# Main.net
KiCad netlist of a schematic drawn in EAGLE
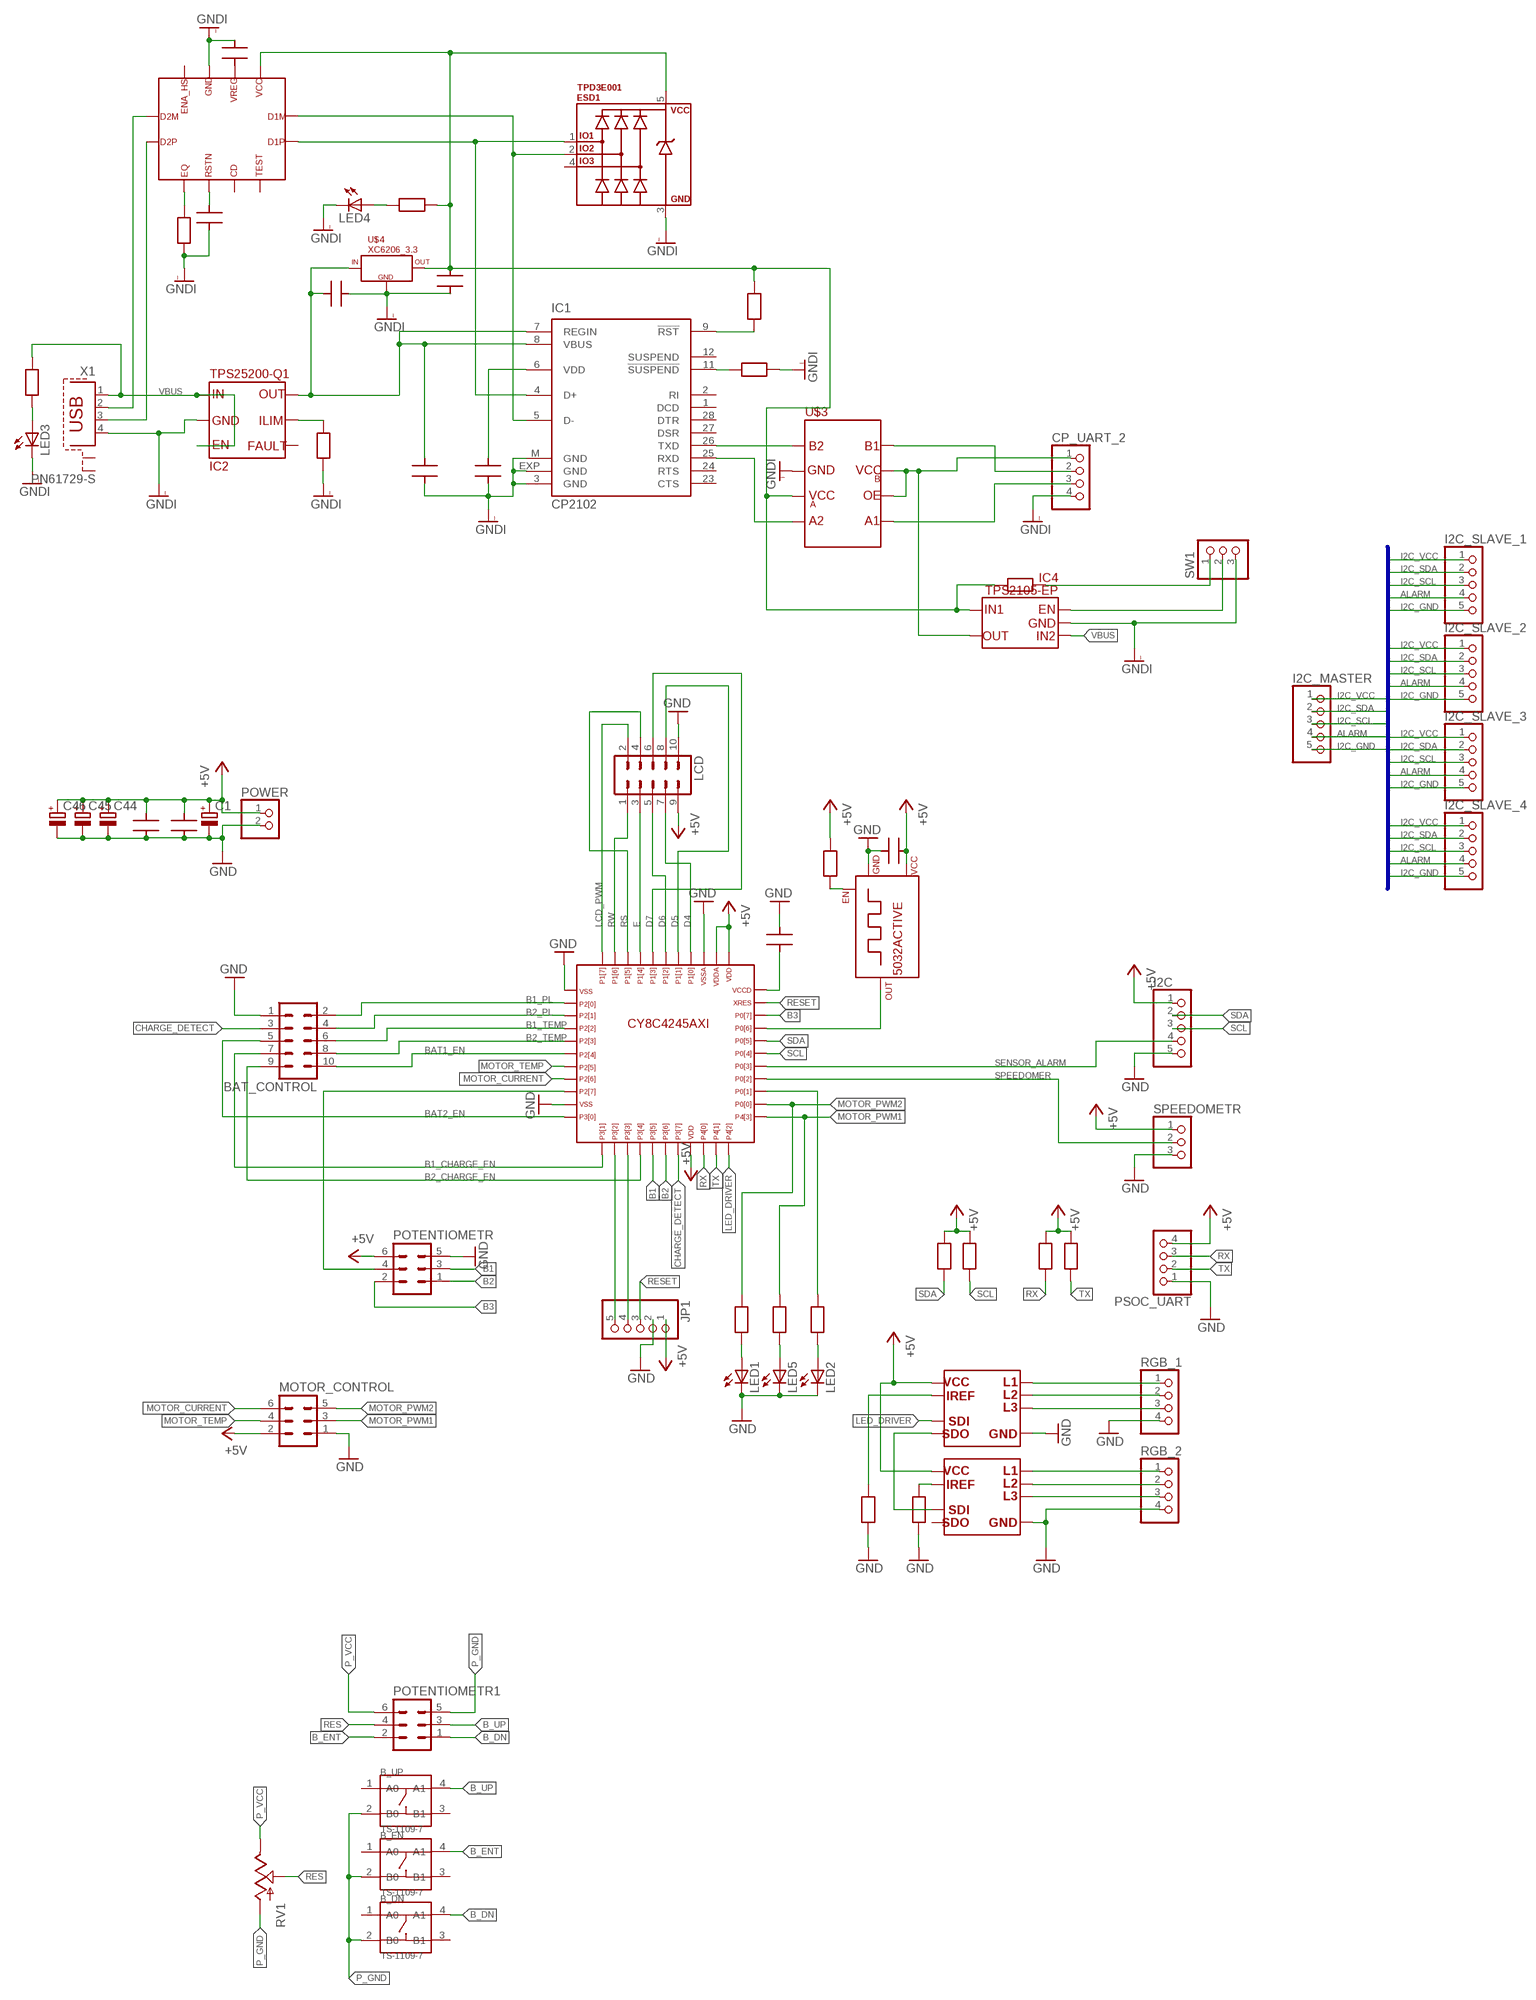
[diagram p0: schematic, sheet 1]
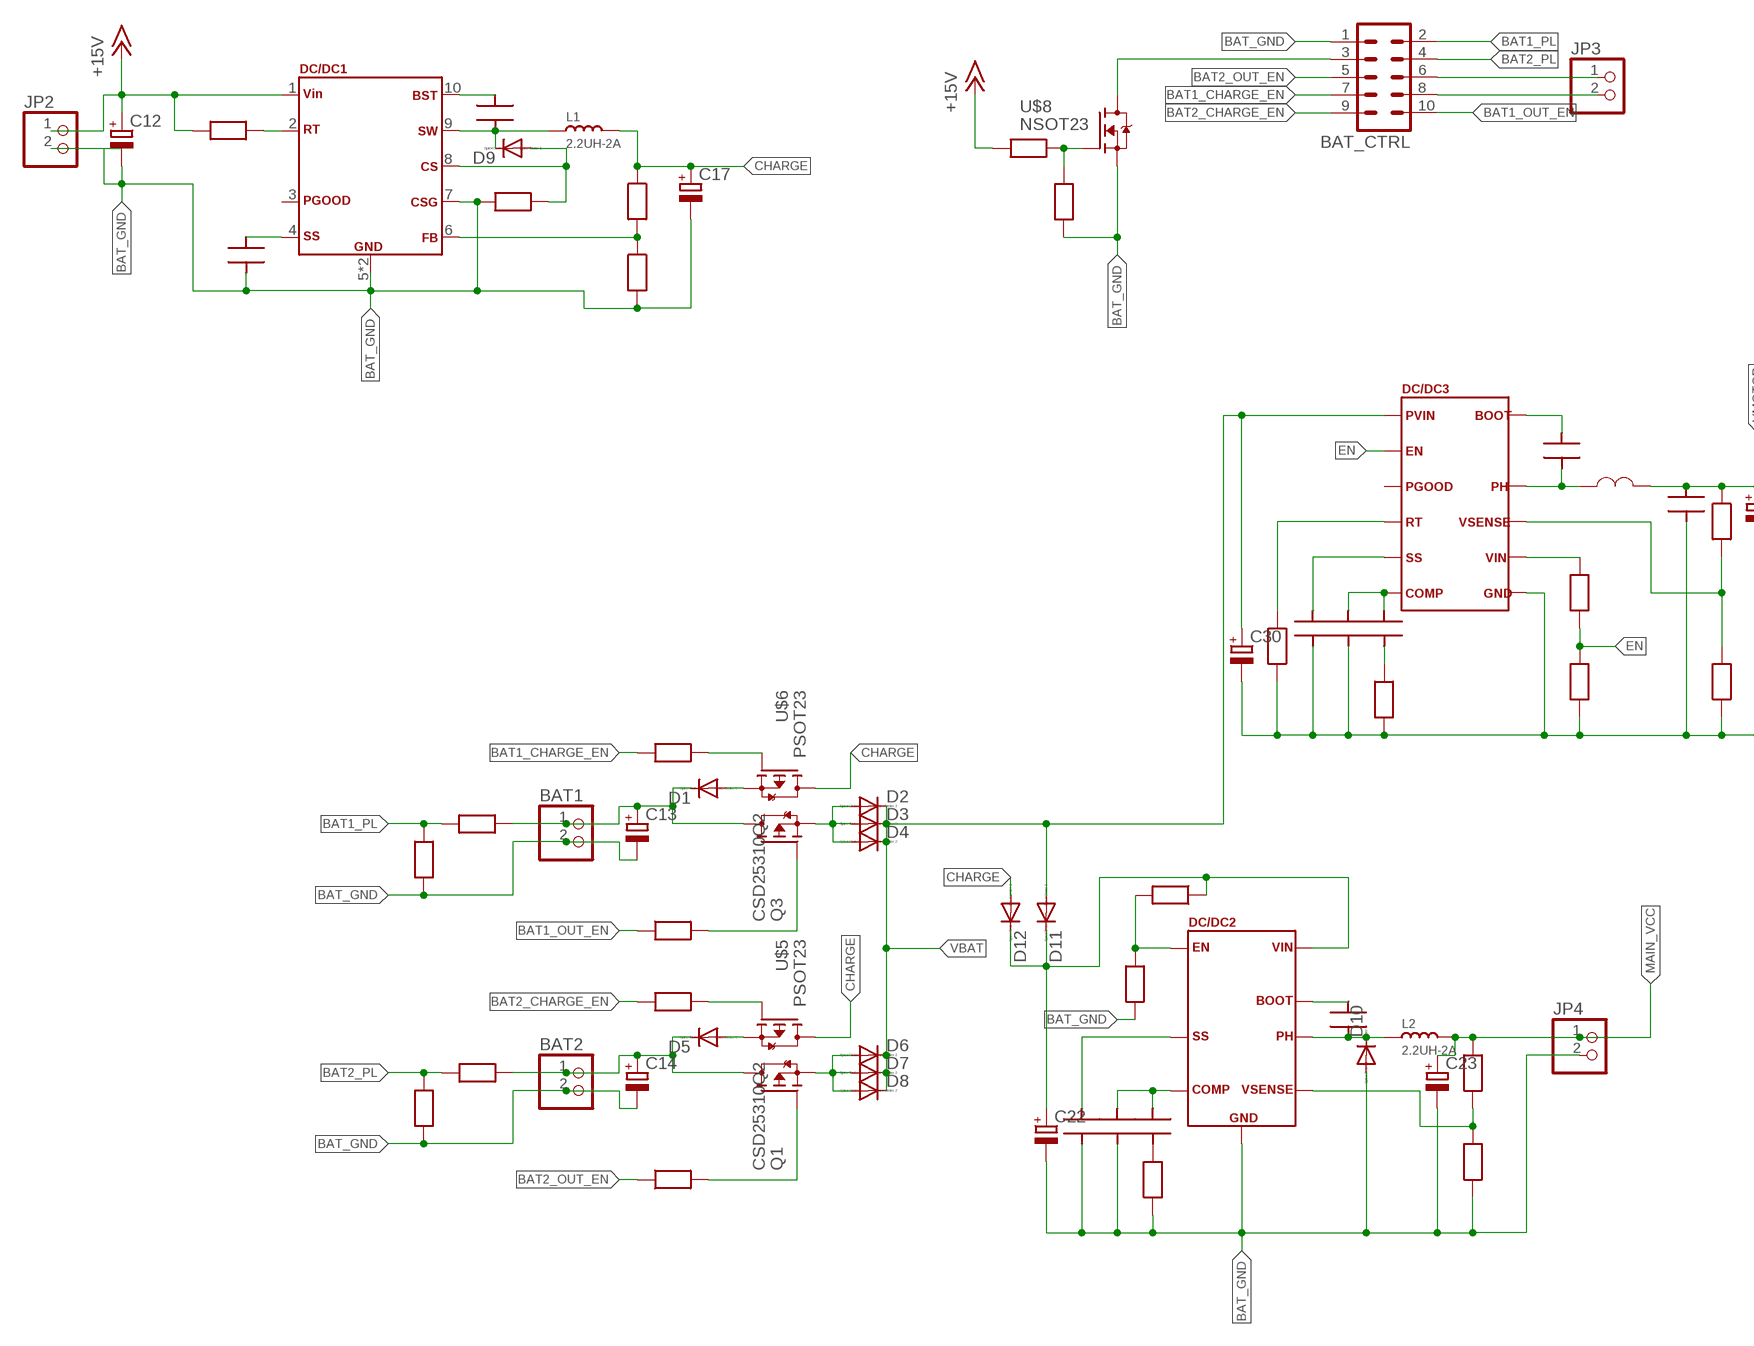
[diagram p1: schematic, sheet 2, part 1 of 2]
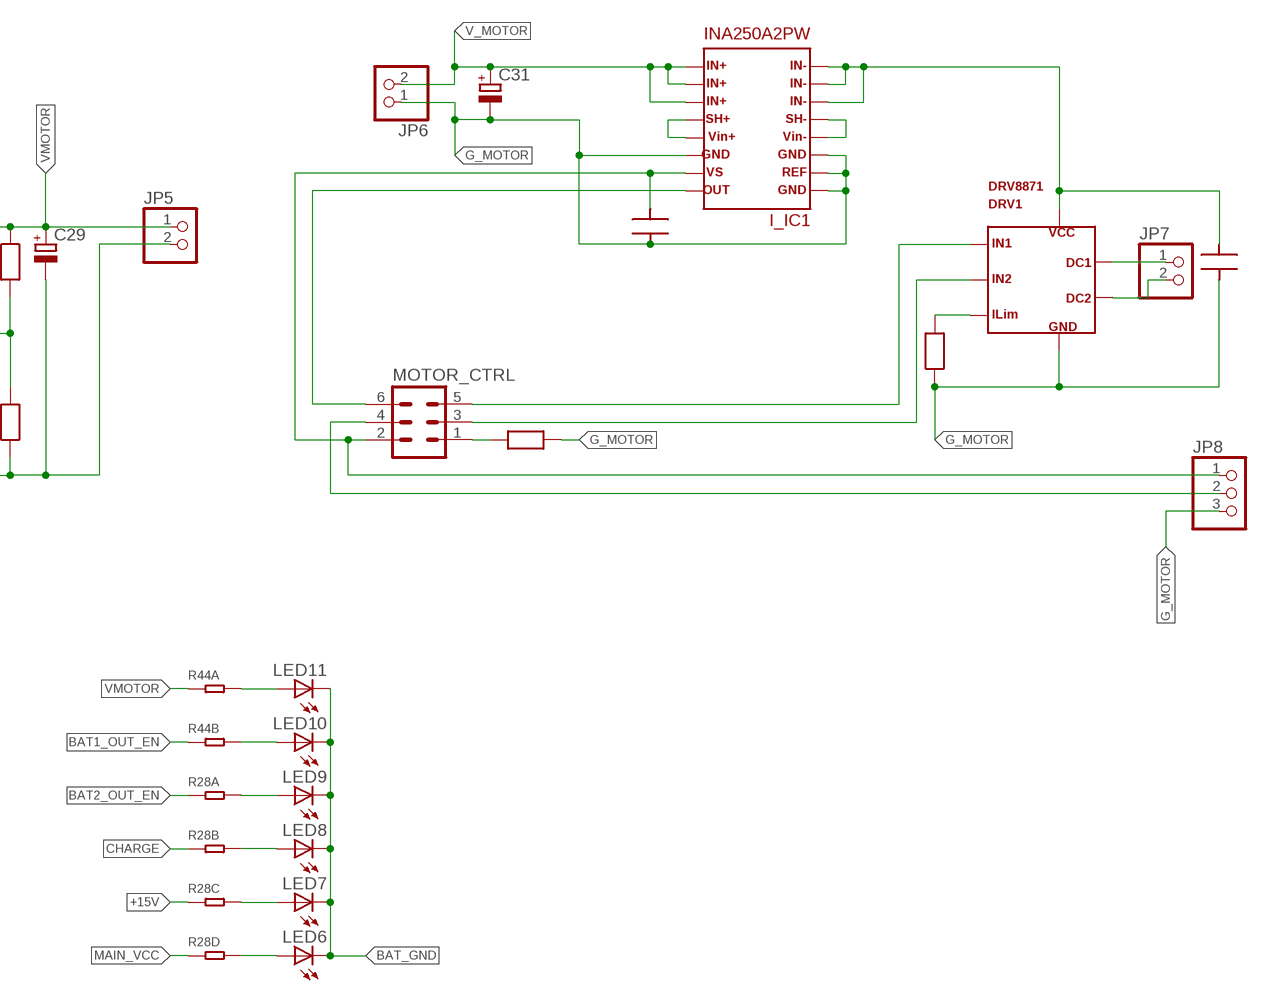
[diagram p2: schematic, sheet 2, part 2 of 2]
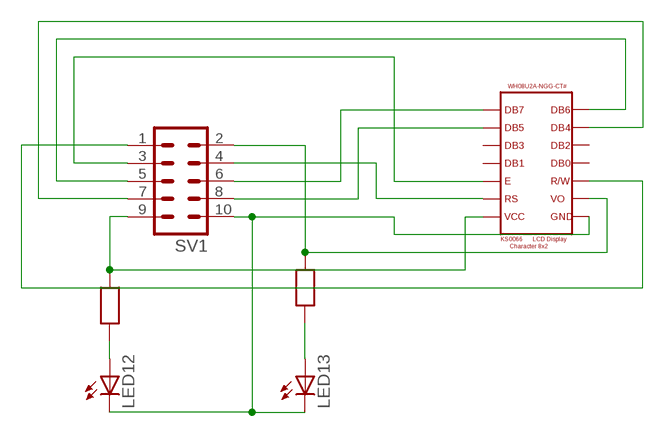
[diagram p3: schematic, sheet 3]
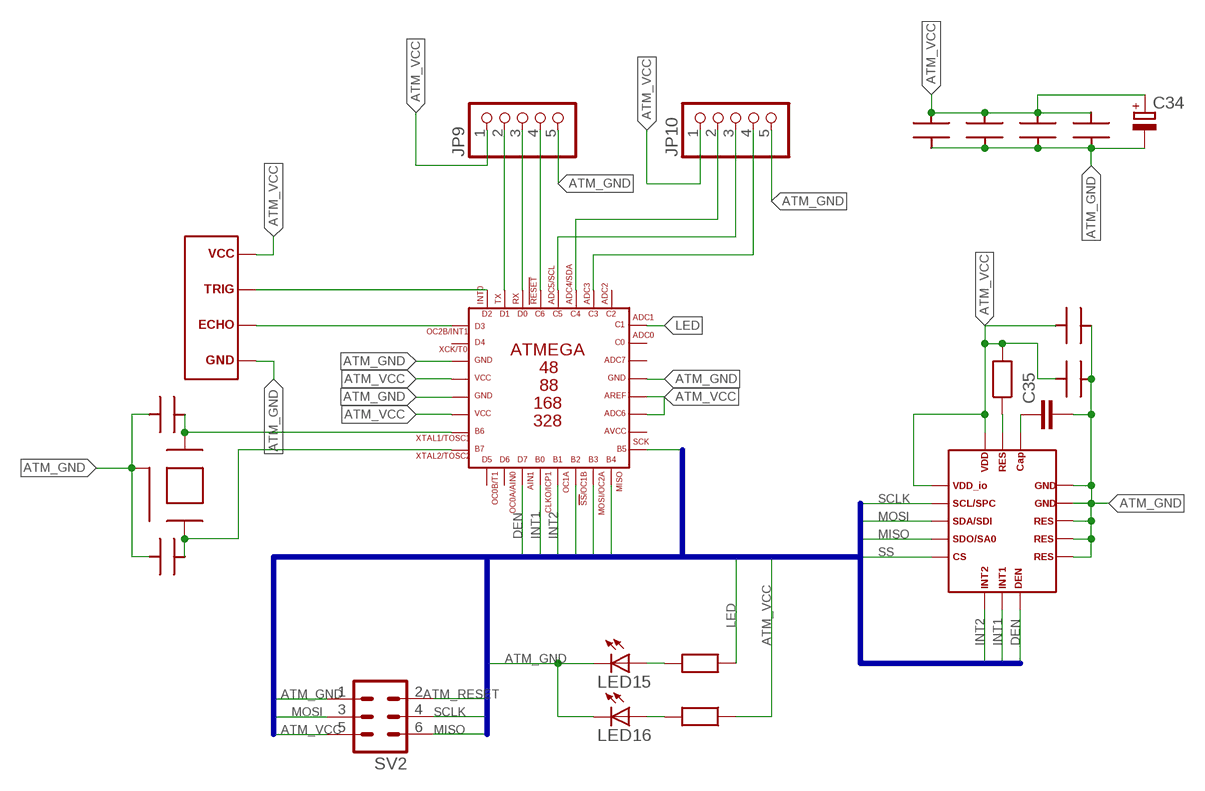
[diagram p4: schematic, sheet 4]

(export (version "E")
  (design (tool "Eeschema 10.0.6"))
  (components
    (comp (ref "LED12")
      (value "LEDCHIPLED_1206")
      (footprint "eagle-import:CHIPLED_1206")
      (libsource (lib "eagle-import") (part "LEDCHIPLED_1206"))
    )
    (comp (ref "LED13")
      (value "LEDCHIPLED_1206")
      (footprint "eagle-import:CHIPLED_1206")
      (libsource (lib "eagle-import") (part "LEDCHIPLED_1206"))
    )
    (comp (ref "R47")
      (value "RES0603")
      (footprint "eagle-import:R0603")
      (libsource (lib "eagle-import") (part "RES0603"))
    )
    (comp (ref "R48")
      (value "RES0603")
      (footprint "eagle-import:R0603")
      (libsource (lib "eagle-import") (part "RES0603"))
    )
    (comp (ref "SV1")
      (value "ML10")
      (footprint "eagle-import:ML10")
      (libsource (lib "eagle-import") (part "ML10"))
    )
    (comp (ref "U$7")
      (value "8X2_KS066")
      (footprint "eagle-import:7X2")
      (libsource (lib "eagle-import") (part "8X2_KS066"))
    )
    (comp (ref "C34")
      (value "CPOL-EU153CLV-0505")
      (footprint "eagle-import:153CLV-0505")
      (libsource (lib "eagle-import") (part "CPOL-EU153CLV-0505"))
    )
    (comp (ref "C35")
      (value "C-EUC1206")
      (footprint "eagle-import:C1206")
      (libsource (lib "eagle-import") (part "C-EUC1206"))
    )
    (comp (ref "C36")
      (value "CAP0603")
      (footprint "eagle-import:C0603")
      (libsource (lib "eagle-import") (part "CAP0603"))
    )
    (comp (ref "C37")
      (value "CAP0603")
      (footprint "eagle-import:C0603")
      (libsource (lib "eagle-import") (part "CAP0603"))
    )
    (comp (ref "C38")
      (value "CAP0603")
      (footprint "eagle-import:C0603")
      (libsource (lib "eagle-import") (part "CAP0603"))
    )
    (comp (ref "C39")
      (value "CAP0603")
      (footprint "eagle-import:C0603")
      (libsource (lib "eagle-import") (part "CAP0603"))
    )
    (comp (ref "C40")
      (value "CAP0603")
      (footprint "eagle-import:C0603")
      (libsource (lib "eagle-import") (part "CAP0603"))
    )
    (comp (ref "C41")
      (value "CAP0603")
      (footprint "eagle-import:C0603")
      (libsource (lib "eagle-import") (part "CAP0603"))
    )
    (comp (ref "C42")
      (value "CAP0603")
      (footprint "eagle-import:C0603")
      (libsource (lib "eagle-import") (part "CAP0603"))
    )
    (comp (ref "C43")
      (value "CAP0603")
      (footprint "eagle-import:C0603")
      (libsource (lib "eagle-import") (part "CAP0603"))
    )
    (comp (ref "GYRO1")
      (value "L3GD20H")
      (footprint "eagle-import:LGA_3X3_16")
      (libsource (lib "eagle-import") (part "L3GD20H"))
    )
    (comp (ref "JP9")
      (value "PINHD-1X5")
      (footprint "eagle-import:1X05")
      (libsource (lib "eagle-import") (part "PINHD-1X5"))
    )
    (comp (ref "JP10")
      (value "PINHD-1X5")
      (footprint "eagle-import:1X05")
      (libsource (lib "eagle-import") (part "PINHD-1X5"))
    )
    (comp (ref "LED15")
      (value "LEDCHIPLED_0603")
      (footprint "eagle-import:CHIPLED_0603")
      (libsource (lib "eagle-import") (part "LEDCHIPLED_0603"))
    )
    (comp (ref "LED16")
      (value "LEDCHIPLED_0603")
      (footprint "eagle-import:CHIPLED_0603")
      (libsource (lib "eagle-import") (part "LEDCHIPLED_0603"))
    )
    (comp (ref "LIDAR1")
      (value "HC-SR04")
      (footprint "eagle-import:HC-SR04")
      (libsource (lib "eagle-import") (part "HC-SR04"))
    )
    (comp (ref "R49")
      (value "RES0603")
      (footprint "eagle-import:R0603")
      (libsource (lib "eagle-import") (part "RES0603"))
    )
    (comp (ref "R50")
      (value "RES0603")
      (footprint "eagle-import:R0603")
      (libsource (lib "eagle-import") (part "RES0603"))
    )
    (comp (ref "R51")
      (value "RES0603")
      (footprint "eagle-import:R0603")
      (libsource (lib "eagle-import") (part "RES0603"))
    )
    (comp (ref "SV2")
      (value "ML6")
      (footprint "eagle-import:ML6")
      (libsource (lib "eagle-import") (part "ML6"))
    )
    (comp (ref "U$9")
      (value "ATMEGAN8")
      (footprint "eagle-import:TQFP32-08")
      (libsource (lib "eagle-import") (part "ATMEGAN8"))
    )
    (comp (ref "U$10")
      (value "3225PASSIVE")
      (footprint "eagle-import:3225")
      (libsource (lib "eagle-import") (part "3225PASSIVE"))
    )
    (comp (ref "BAT_CONTROL")
      (value "ML10")
      (footprint "eagle-import:ML10")
      (libsource (lib "eagle-import") (part "ML10"))
    )
    (comp (ref "B_DN")
      (value "TS-1109-7")
      (footprint "eagle-import:SW4-6.2X6.2X5.0MM")
      (libsource (lib "eagle-import") (part "DIP-BUTTON-TOP-BLACK(4P-D6.2MM)"))
    )
    (comp (ref "B_EN")
      (value "TS-1109-7")
      (footprint "eagle-import:SW4-6.2X6.2X5.0MM")
      (libsource (lib "eagle-import") (part "DIP-BUTTON-TOP-BLACK(4P-D6.2MM)"))
    )
    (comp (ref "B_UP")
      (value "TS-1109-7")
      (footprint "eagle-import:SW4-6.2X6.2X5.0MM")
      (libsource (lib "eagle-import") (part "DIP-BUTTON-TOP-BLACK(4P-D6.2MM)"))
    )
    (comp (ref "C1")
      (value "CPOL-EU150CLZ-0810")
      (footprint "eagle-import:150CLZ-0810")
      (libsource (lib "eagle-import") (part "CPOL-EU150CLZ-0810"))
    )
    (comp (ref "C2")
      (value "CAP0603")
      (footprint "eagle-import:C0603")
      (libsource (lib "eagle-import") (part "CAP0603"))
    )
    (comp (ref "C3")
      (value "CAP0603")
      (footprint "eagle-import:C0603")
      (libsource (lib "eagle-import") (part "CAP0603"))
    )
    (comp (ref "C4")
      (value "CAP0603")
      (footprint "eagle-import:C0603")
      (libsource (lib "eagle-import") (part "CAP0603"))
    )
    (comp (ref "C5")
      (value "CAP0603")
      (footprint "eagle-import:C0603")
      (libsource (lib "eagle-import") (part "CAP0603"))
    )
    (comp (ref "C6")
      (value "CAP0603")
      (footprint "eagle-import:C0603")
      (libsource (lib "eagle-import") (part "CAP0603"))
    )
    (comp (ref "C7")
      (value "CAP0603")
      (footprint "eagle-import:C0603")
      (libsource (lib "eagle-import") (part "CAP0603"))
    )
    (comp (ref "C8")
      (value "CAP0603")
      (footprint "eagle-import:C0603")
      (libsource (lib "eagle-import") (part "CAP0603"))
    )
    (comp (ref "C9")
      (value "CAP0603")
      (footprint "eagle-import:C0603")
      (libsource (lib "eagle-import") (part "CAP0603"))
    )
    (comp (ref "C10")
      (value "CAP0603")
      (footprint "eagle-import:C0603")
      (libsource (lib "eagle-import") (part "CAP0603"))
    )
    (comp (ref "C11")
      (value "CAP0603")
      (footprint "eagle-import:C0603")
      (libsource (lib "eagle-import") (part "CAP0603"))
    )
    (comp (ref "C44")
      (value "CPOL-EU150CLZ-0810")
      (footprint "eagle-import:150CLZ-0810")
      (libsource (lib "eagle-import") (part "CPOL-EU150CLZ-0810"))
    )
    (comp (ref "C45")
      (value "CPOL-EUSMCD")
      (footprint "eagle-import:SMC_D")
      (libsource (lib "eagle-import") (part "CPOL-EUSMCD"))
    )
    (comp (ref "C46")
      (value "CPOL-EUSMCD")
      (footprint "eagle-import:SMC_D")
      (libsource (lib "eagle-import") (part "CPOL-EUSMCD"))
    )
    (comp (ref "CP_UART_2")
      (value "PINHD-1X4")
      (footprint "eagle-import:1X04")
      (libsource (lib "eagle-import") (part "PINHD-1X4"))
    )
    (comp (ref "ESD1")
      (value "TPD3E001")
      (footprint "eagle-import:SOT23-5")
      (libsource (lib "eagle-import") (part "TPD3E001"))
    )
    (comp (ref "I2C")
      (value "PINHD-1X5")
      (footprint "eagle-import:1X05")
      (libsource (lib "eagle-import") (part "PINHD-1X5"))
    )
    (comp (ref "I2C_MASTER")
      (value "PINHD-1X5")
      (footprint "eagle-import:1X05")
      (libsource (lib "eagle-import") (part "PINHD-1X5"))
    )
    (comp (ref "I2C_SLAVE_1")
      (value "PINHD-1X5")
      (footprint "eagle-import:1X05")
      (libsource (lib "eagle-import") (part "PINHD-1X5"))
    )
    (comp (ref "I2C_SLAVE_2")
      (value "PINHD-1X5")
      (footprint "eagle-import:1X05")
      (libsource (lib "eagle-import") (part "PINHD-1X5"))
    )
    (comp (ref "I2C_SLAVE_3")
      (value "PINHD-1X5")
      (footprint "eagle-import:1X05")
      (libsource (lib "eagle-import") (part "PINHD-1X5"))
    )
    (comp (ref "I2C_SLAVE_4")
      (value "PINHD-1X5")
      (footprint "eagle-import:1X05")
      (libsource (lib "eagle-import") (part "PINHD-1X5"))
    )
    (comp (ref "IC1")
      (value "CP2102")
      (footprint "eagle-import:MLP28")
      (fields (field (name "MF") "FARNELL") (field (name "MPN") "CP2102-GM"))
      (libsource (lib "eagle-import") (part "CP2102"))
    )
    (comp (ref "IC2")
      (value "TPS25200-Q1")
      (footprint "eagle-import:PWSON6")
      (libsource (lib "eagle-import") (part "TPS25200-Q1"))
    )
    (comp (ref "IC4")
      (value "TPS2105-EP")
      (footprint "eagle-import:SOT23-5")
      (libsource (lib "eagle-import") (part "TPS2105-EP"))
    )
    (comp (ref "JP1")
      (value "PINHD-1X5")
      (footprint "eagle-import:1X05")
      (libsource (lib "eagle-import") (part "PINHD-1X5"))
    )
    (comp (ref "LCD")
      (value "ML10")
      (footprint "eagle-import:ML10")
      (libsource (lib "eagle-import") (part "ML10"))
    )
    (comp (ref "LED1")
      (value "LEDCHIP-LED0603")
      (footprint "eagle-import:CHIP-LED0603")
      (libsource (lib "eagle-import") (part "LEDCHIP-LED0603"))
    )
    (comp (ref "LED2")
      (value "LEDCHIP-LED0603")
      (footprint "eagle-import:CHIP-LED0603")
      (libsource (lib "eagle-import") (part "LEDCHIP-LED0603"))
    )
    (comp (ref "LED3")
      (value "LEDCHIP-LED0805")
      (footprint "eagle-import:CHIP-LED0805")
      (libsource (lib "eagle-import") (part "LEDCHIP-LED0805"))
    )
    (comp (ref "LED4")
      (value "LEDCHIP-LED0805")
      (footprint "eagle-import:CHIP-LED0805")
      (libsource (lib "eagle-import") (part "LEDCHIP-LED0805"))
    )
    (comp (ref "LED5")
      (value "LEDCHIP-LED0603")
      (footprint "eagle-import:CHIP-LED0603")
      (libsource (lib "eagle-import") (part "LEDCHIP-LED0603"))
    )
    (comp (ref "LED_DR1")
      (value "TLC5973")
      (footprint "eagle-import:SOIC8-1.27-5X4MM")
      (libsource (lib "eagle-import") (part "TLC5973"))
    )
    (comp (ref "LED_DR2")
      (value "TLC5973")
      (footprint "eagle-import:SOIC8-1.27-5X4MM")
      (libsource (lib "eagle-import") (part "TLC5973"))
    )
    (comp (ref "MOTOR_CONTROL")
      (value "ML6")
      (footprint "eagle-import:ML6")
      (libsource (lib "eagle-import") (part "ML6"))
    )
    (comp (ref "POTENTIOMETR")
      (value "ML6")
      (footprint "eagle-import:ML6")
      (libsource (lib "eagle-import") (part "ML6"))
    )
    (comp (ref "POTENTIOMETR1")
      (value "ML6")
      (footprint "eagle-import:ML6")
      (libsource (lib "eagle-import") (part "ML6"))
    )
    (comp (ref "POWER")
      (value "PINHD-1X2")
      (footprint "eagle-import:1X02")
      (libsource (lib "eagle-import") (part "PINHD-1X2"))
    )
    (comp (ref "PSOC_UART")
      (value "PINHD-1X4")
      (footprint "eagle-import:1X04")
      (libsource (lib "eagle-import") (part "PINHD-1X4"))
    )
    (comp (ref "R1")
      (value "RES0603")
      (footprint "eagle-import:R0603")
      (libsource (lib "eagle-import") (part "RES0603"))
    )
    (comp (ref "R2")
      (value "RES0603")
      (footprint "eagle-import:R0603")
      (libsource (lib "eagle-import") (part "RES0603"))
    )
    (comp (ref "R3")
      (value "RES0603")
      (footprint "eagle-import:R0603")
      (libsource (lib "eagle-import") (part "RES0603"))
    )
    (comp (ref "R4")
      (value "RES0603")
      (footprint "eagle-import:R0603")
      (libsource (lib "eagle-import") (part "RES0603"))
    )
    (comp (ref "R5")
      (value "RES0603")
      (footprint "eagle-import:R0603")
      (libsource (lib "eagle-import") (part "RES0603"))
    )
    (comp (ref "R6")
      (value "RES0603")
      (footprint "eagle-import:R0603")
      (libsource (lib "eagle-import") (part "RES0603"))
    )
    (comp (ref "R7")
      (value "RES0603")
      (footprint "eagle-import:R0603")
      (libsource (lib "eagle-import") (part "RES0603"))
    )
    (comp (ref "R8")
      (value "RES0603")
      (footprint "eagle-import:R0603")
      (libsource (lib "eagle-import") (part "RES0603"))
    )
    (comp (ref "R9")
      (value "RES0603")
      (footprint "eagle-import:R0603")
      (libsource (lib "eagle-import") (part "RES0603"))
    )
    (comp (ref "R10")
      (value "RES0603")
      (footprint "eagle-import:R0603")
      (libsource (lib "eagle-import") (part "RES0603"))
    )
    (comp (ref "R11")
      (value "RES0603")
      (footprint "eagle-import:R0603")
      (libsource (lib "eagle-import") (part "RES0603"))
    )
    (comp (ref "R12")
      (value "RES0603")
      (footprint "eagle-import:R0603")
      (libsource (lib "eagle-import") (part "RES0603"))
    )
    (comp (ref "R13")
      (value "RES0603")
      (footprint "eagle-import:R0603")
      (libsource (lib "eagle-import") (part "RES0603"))
    )
    (comp (ref "R14")
      (value "RES0603")
      (footprint "eagle-import:R0603")
      (libsource (lib "eagle-import") (part "RES0603"))
    )
    (comp (ref "R15")
      (value "RES0603")
      (footprint "eagle-import:R0603")
      (libsource (lib "eagle-import") (part "RES0603"))
    )
    (comp (ref "R16")
      (value "RES0603")
      (footprint "eagle-import:R0603")
      (libsource (lib "eagle-import") (part "RES0603"))
    )
    (comp (ref "R41")
      (value "RES0603")
      (footprint "eagle-import:R0603")
      (libsource (lib "eagle-import") (part "RES0603"))
    )
    (comp (ref "RGB_1")
      (value "PINHD-1X4")
      (footprint "eagle-import:1X04")
      (libsource (lib "eagle-import") (part "PINHD-1X4"))
    )
    (comp (ref "RGB_2")
      (value "PINHD-1X4")
      (footprint "eagle-import:1X04")
      (libsource (lib "eagle-import") (part "PINHD-1X4"))
    )
    (comp (ref "RV1")
      (value "POT")
      (footprint "eagle-import:ALPS_POT")
      (libsource (lib "eagle-import") (part "POT"))
    )
    (comp (ref "SPEEDOMETR")
      (value "PINHD-1X3")
      (footprint "eagle-import:1X03")
      (libsource (lib "eagle-import") (part "PINHD-1X3"))
    )
    (comp (ref "SW1")
      (value "PINHD-1X3")
      (footprint "eagle-import:1X03")
      (libsource (lib "eagle-import") (part "PINHD-1X3"))
    )
    (comp (ref "U$1")
      (value "CY8C4245")
      (footprint "eagle-import:TQFP44_CY_LOGO")
      (libsource (lib "eagle-import") (part "CY8C4245"))
    )
    (comp (ref "U$2")
      (value "5032ACTIVE")
      (footprint "eagle-import:5030A")
      (libsource (lib "eagle-import") (part "5032ACTIVE"))
    )
    (comp (ref "U$3")
      (value "TXS0102_SM8")
      (footprint "eagle-import:SM8")
      (libsource (lib "eagle-import") (part "TXS0102_SM8"))
    )
    (comp (ref "U$4")
      (value "XC6206_3.3")
      (footprint "eagle-import:SOT23")
      (libsource (lib "eagle-import") (part "XC6206_3.3"))
    )
    (comp (ref "USB1")
      (value "TUSB211QRWBRQ1")
      (footprint "eagle-import:X2QFN")
      (libsource (lib "eagle-import") (part "TUSB211QRWBRQ1"))
    )
    (comp (ref "X1")
      (value "PN61729-S")
      (footprint "eagle-import:PN61729-S")
      (libsource (lib "eagle-import") (part "PN61729-S"))
    )
    (comp (ref "BAT1")
      (value "PINHD-1X2")
      (footprint "eagle-import:1X02")
      (libsource (lib "eagle-import") (part "PINHD-1X2"))
    )
    (comp (ref "BAT2")
      (value "PINHD-1X2")
      (footprint "eagle-import:1X02")
      (libsource (lib "eagle-import") (part "PINHD-1X2"))
    )
    (comp (ref "BAT_CTRL")
      (value "ML10")
      (footprint "eagle-import:ML10")
      (libsource (lib "eagle-import") (part "ML10"))
    )
    (comp (ref "C12")
      (value "CPOL-EU153CLV-0810")
      (footprint "eagle-import:153CLV-0810")
      (libsource (lib "eagle-import") (part "CPOL-EU153CLV-0810"))
    )
    (comp (ref "C13")
      (value "CPOL-EU153CLV-0810")
      (footprint "eagle-import:153CLV-0810")
      (libsource (lib "eagle-import") (part "CPOL-EU153CLV-0810"))
    )
    (comp (ref "C14")
      (value "CPOL-EU153CLV-0810")
      (footprint "eagle-import:153CLV-0810")
      (libsource (lib "eagle-import") (part "CPOL-EU153CLV-0810"))
    )
    (comp (ref "C15")
      (value "CAP0603")
      (footprint "eagle-import:C0603")
      (libsource (lib "eagle-import") (part "CAP0603"))
    )
    (comp (ref "C16")
      (value "CAP0603")
      (footprint "eagle-import:C0603")
      (libsource (lib "eagle-import") (part "CAP0603"))
    )
    (comp (ref "C17")
      (value "CPOL-EU153CLV-0505")
      (footprint "eagle-import:153CLV-0505")
      (libsource (lib "eagle-import") (part "CPOL-EU153CLV-0505"))
    )
    (comp (ref "C18")
      (value "CAP0603")
      (footprint "eagle-import:C0603")
      (libsource (lib "eagle-import") (part "CAP0603"))
    )
    (comp (ref "C19")
      (value "CAP0603")
      (footprint "eagle-import:C0603")
      (libsource (lib "eagle-import") (part "CAP0603"))
    )
    (comp (ref "C20")
      (value "CAP0603")
      (footprint "eagle-import:C0603")
      (libsource (lib "eagle-import") (part "CAP0603"))
    )
    (comp (ref "C21")
      (value "CAP0603")
      (footprint "eagle-import:C0603")
      (libsource (lib "eagle-import") (part "CAP0603"))
    )
    (comp (ref "C22")
      (value "CPOL-EU153CLV-0505")
      (footprint "eagle-import:153CLV-0505")
      (libsource (lib "eagle-import") (part "CPOL-EU153CLV-0505"))
    )
    (comp (ref "C23")
      (value "CPOL-EU153CLV-0505")
      (footprint "eagle-import:153CLV-0505")
      (libsource (lib "eagle-import") (part "CPOL-EU153CLV-0505"))
    )
    (comp (ref "C24")
      (value "CAP0603")
      (footprint "eagle-import:C0603")
      (libsource (lib "eagle-import") (part "CAP0603"))
    )
    (comp (ref "C25")
      (value "CAP0603")
      (footprint "eagle-import:C0603")
      (libsource (lib "eagle-import") (part "CAP0603"))
    )
    (comp (ref "C26")
      (value "CAP0603")
      (footprint "eagle-import:C0603")
      (libsource (lib "eagle-import") (part "CAP0603"))
    )
    (comp (ref "C27")
      (value "CAP0603")
      (footprint "eagle-import:C0603")
      (libsource (lib "eagle-import") (part "CAP0603"))
    )
    (comp (ref "C28")
      (value "CAP0603")
      (footprint "eagle-import:C0603")
      (libsource (lib "eagle-import") (part "CAP0603"))
    )
    (comp (ref "C29")
      (value "CPOL-EU153CLV-0505")
      (footprint "eagle-import:153CLV-0505")
      (libsource (lib "eagle-import") (part "CPOL-EU153CLV-0505"))
    )
    (comp (ref "C30")
      (value "CPOL-EU153CLV-0505")
      (footprint "eagle-import:153CLV-0505")
      (libsource (lib "eagle-import") (part "CPOL-EU153CLV-0505"))
    )
    (comp (ref "C31")
      (value "CPOL-EU153CLV-0505")
      (footprint "eagle-import:153CLV-0505")
      (libsource (lib "eagle-import") (part "CPOL-EU153CLV-0505"))
    )
    (comp (ref "C32")
      (value "CAP0603")
      (footprint "eagle-import:C0603")
      (libsource (lib "eagle-import") (part "CAP0603"))
    )
    (comp (ref "C33")
      (value "CAP0603")
      (footprint "eagle-import:C0603")
      (libsource (lib "eagle-import") (part "CAP0603"))
    )
    (comp (ref "D1")
      (value "DIODE-DO-214AC")
      (footprint "eagle-import:DO-214AC")
      (libsource (lib "eagle-import") (part "DIODE-DO-214AC"))
    )
    (comp (ref "D2")
      (value "DIODE-DO-214AC")
      (footprint "eagle-import:DO-214AC")
      (libsource (lib "eagle-import") (part "DIODE-DO-214AC"))
    )
    (comp (ref "D3")
      (value "DIODE-DO-214AC")
      (footprint "eagle-import:DO-214AC")
      (libsource (lib "eagle-import") (part "DIODE-DO-214AC"))
    )
    (comp (ref "D4")
      (value "DIODE-DO-214AC")
      (footprint "eagle-import:DO-214AC")
      (libsource (lib "eagle-import") (part "DIODE-DO-214AC"))
    )
    (comp (ref "D5")
      (value "DIODE-DO-214AC")
      (footprint "eagle-import:DO-214AC")
      (libsource (lib "eagle-import") (part "DIODE-DO-214AC"))
    )
    (comp (ref "D6")
      (value "DIODE-DO-214AC")
      (footprint "eagle-import:DO-214AC")
      (libsource (lib "eagle-import") (part "DIODE-DO-214AC"))
    )
    (comp (ref "D7")
      (value "DIODE-DO-214AC")
      (footprint "eagle-import:DO-214AC")
      (libsource (lib "eagle-import") (part "DIODE-DO-214AC"))
    )
    (comp (ref "D8")
      (value "DIODE-DO-214AC")
      (footprint "eagle-import:DO-214AC")
      (libsource (lib "eagle-import") (part "DIODE-DO-214AC"))
    )
    (comp (ref "D9")
      (value "DIODE-MELF-MLL41")
      (footprint "eagle-import:MELF-MLL41")
      (libsource (lib "eagle-import") (part "DIODE-MELF-MLL41"))
    )
    (comp (ref "D10")
      (value "DIODE-DO-214AC")
      (footprint "eagle-import:DO-214AC")
      (libsource (lib "eagle-import") (part "DIODE-DO-214AC"))
    )
    (comp (ref "D11")
      (value "DIODE-DO-214AC")
      (footprint "eagle-import:DO-214AC")
      (libsource (lib "eagle-import") (part "DIODE-DO-214AC"))
    )
    (comp (ref "D12")
      (value "DIODE-DO-214AC")
      (footprint "eagle-import:DO-214AC")
      (libsource (lib "eagle-import") (part "DIODE-DO-214AC"))
    )
    (comp (ref "DC/DC1")
      (value "LM25011")
      (footprint "eagle-import:HVSSOP-10")
      (libsource (lib "eagle-import") (part "LM25011"))
    )
    (comp (ref "DC/DC2")
      (value "TPS54232")
      (footprint "eagle-import:SOIC8-1.27-5X4MM")
      (libsource (lib "eagle-import") (part "TPS54232"))
    )
    (comp (ref "DC/DC3")
      (value "TPS54622")
      (footprint "eagle-import:VQFN-14_PWR")
      (libsource (lib "eagle-import") (part "TPS54622"))
    )
    (comp (ref "DRV1")
      (value "DRV8871")
      (footprint "eagle-import:HTSOP8")
      (libsource (lib "eagle-import") (part "DRV8871"))
    )
    (comp (ref "I_IC1")
      (value "INA250A2PW")
      (footprint "eagle-import:SSOP16")
      (libsource (lib "eagle-import") (part "INA250A2PW"))
    )
    (comp (ref "JP2")
      (value "PINHD-1X2")
      (footprint "eagle-import:1X02")
      (libsource (lib "eagle-import") (part "PINHD-1X2"))
    )
    (comp (ref "JP3")
      (value "PINHD-1X2")
      (footprint "eagle-import:1X02")
      (libsource (lib "eagle-import") (part "PINHD-1X2"))
    )
    (comp (ref "JP4")
      (value "PINHD-1X2")
      (footprint "eagle-import:1X02")
      (libsource (lib "eagle-import") (part "PINHD-1X2"))
    )
    (comp (ref "JP5")
      (value "PINHD-1X2")
      (footprint "eagle-import:1X02")
      (libsource (lib "eagle-import") (part "PINHD-1X2"))
    )
    (comp (ref "JP6")
      (value "PINHD-1X2")
      (footprint "eagle-import:1X02")
      (libsource (lib "eagle-import") (part "PINHD-1X2"))
    )
    (comp (ref "JP7")
      (value "PINHD-1X2")
      (footprint "eagle-import:1X02")
      (libsource (lib "eagle-import") (part "PINHD-1X2"))
    )
    (comp (ref "JP8")
      (value "PINHD-1X3")
      (footprint "eagle-import:1X03")
      (libsource (lib "eagle-import") (part "PINHD-1X3"))
    )
    (comp (ref "L$1")
      (value "LDCP")
      (footprint "eagle-import:LDCP")
      (libsource (lib "eagle-import") (part "LDCP"))
    )
    (comp (ref "L1")
      (value "2.2UH-2A")
      (footprint "eagle-import:INT2-SMD-4.8X4.6X1.0MM")
      (fields (field (name "MPN") "VLF5010ST-2R2M2R0"))
      (libsource (lib "eagle-import") (part "SMD-INDUCTOR-2.2UH-20%-2A(2P-4.8X4.6MM)"))
    )
    (comp (ref "L2")
      (value "2.2UH-2A")
      (footprint "eagle-import:INT2-SMD-4.8X4.6X1.0MM")
      (fields (field (name "MPN") "VLF5010ST-2R2M2R0"))
      (libsource (lib "eagle-import") (part "SMD-INDUCTOR-2.2UH-20%-2A(2P-4.8X4.6MM)"))
    )
    (comp (ref "LED6")
      (value "LEDCHIPLED_1206")
      (footprint "eagle-import:CHIPLED_1206")
      (libsource (lib "eagle-import") (part "LEDCHIPLED_1206"))
    )
    (comp (ref "LED7")
      (value "LEDCHIPLED_1206")
      (footprint "eagle-import:CHIPLED_1206")
      (libsource (lib "eagle-import") (part "LEDCHIPLED_1206"))
    )
    (comp (ref "LED8")
      (value "LEDCHIPLED_1206")
      (footprint "eagle-import:CHIPLED_1206")
      (libsource (lib "eagle-import") (part "LEDCHIPLED_1206"))
    )
    (comp (ref "LED9")
      (value "LEDCHIPLED_1206")
      (footprint "eagle-import:CHIPLED_1206")
      (libsource (lib "eagle-import") (part "LEDCHIPLED_1206"))
    )
    (comp (ref "LED10")
      (value "LEDCHIPLED_1206")
      (footprint "eagle-import:CHIPLED_1206")
      (libsource (lib "eagle-import") (part "LEDCHIPLED_1206"))
    )
    (comp (ref "LED11")
      (value "LEDCHIPLED_1206")
      (footprint "eagle-import:CHIPLED_1206")
      (libsource (lib "eagle-import") (part "LEDCHIPLED_1206"))
    )
    (comp (ref "MOTOR_CTRL")
      (value "ML6")
      (footprint "eagle-import:ML6")
      (libsource (lib "eagle-import") (part "ML6"))
    )
    (comp (ref "Q1")
      (value "CSD25310Q2")
      (footprint "eagle-import:SON_Q2")
      (libsource (lib "eagle-import") (part "CSD25310Q2"))
    )
    (comp (ref "Q3")
      (value "CSD25310Q2")
      (footprint "eagle-import:SON_Q2")
      (libsource (lib "eagle-import") (part "CSD25310Q2"))
    )
    (comp (ref "R17")
      (value "RES0603")
      (footprint "eagle-import:R0603")
      (libsource (lib "eagle-import") (part "RES0603"))
    )
    (comp (ref "R18")
      (value "RES0603")
      (footprint "eagle-import:R0603")
      (libsource (lib "eagle-import") (part "RES0603"))
    )
    (comp (ref "R19")
      (value "RES0603")
      (footprint "eagle-import:R0603")
      (libsource (lib "eagle-import") (part "RES0603"))
    )
    (comp (ref "R20")
      (value "RES0603")
      (footprint "eagle-import:R0603")
      (libsource (lib "eagle-import") (part "RES0603"))
    )
    (comp (ref "R21")
      (value "RES0603")
      (footprint "eagle-import:R0603")
      (libsource (lib "eagle-import") (part "RES0603"))
    )
    (comp (ref "R22")
      (value "RES0603")
      (footprint "eagle-import:R0603")
      (libsource (lib "eagle-import") (part "RES0603"))
    )
    (comp (ref "R23")
      (value "RES0603")
      (footprint "eagle-import:R0603")
      (libsource (lib "eagle-import") (part "RES0603"))
    )
    (comp (ref "R24")
      (value "RES0603")
      (footprint "eagle-import:R0603")
      (libsource (lib "eagle-import") (part "RES0603"))
    )
    (comp (ref "R25")
      (value "RES0603")
      (footprint "eagle-import:R0603")
      (libsource (lib "eagle-import") (part "RES0603"))
    )
    (comp (ref "R26")
      (value "RES0603")
      (footprint "eagle-import:R0603")
      (libsource (lib "eagle-import") (part "RES0603"))
    )
    (comp (ref "R27")
      (value "RES0603")
      (footprint "eagle-import:R0603")
      (libsource (lib "eagle-import") (part "RES0603"))
    )
    (comp (ref "R28")
      (value "RES-ARRAY-1206")
      (footprint "eagle-import:RA1206-8")
      (libsource (lib "eagle-import") (part "RES-ARRAY-1206"))
    )
    (comp (ref "R29")
      (value "RES0603")
      (footprint "eagle-import:R0603")
      (libsource (lib "eagle-import") (part "RES0603"))
    )
    (comp (ref "R30")
      (value "RES0603")
      (footprint "eagle-import:R0603")
      (libsource (lib "eagle-import") (part "RES0603"))
    )
    (comp (ref "R31")
      (value "RES0603")
      (footprint "eagle-import:R0603")
      (libsource (lib "eagle-import") (part "RES0603"))
    )
    (comp (ref "R32")
      (value "RES0603")
      (footprint "eagle-import:R0603")
      (libsource (lib "eagle-import") (part "RES0603"))
    )
    (comp (ref "R33")
      (value "RES0603")
      (footprint "eagle-import:R0603")
      (libsource (lib "eagle-import") (part "RES0603"))
    )
    (comp (ref "R34")
      (value "RES0603")
      (footprint "eagle-import:R0603")
      (libsource (lib "eagle-import") (part "RES0603"))
    )
    (comp (ref "R35")
      (value "RES0603")
      (footprint "eagle-import:R0603")
      (libsource (lib "eagle-import") (part "RES0603"))
    )
    (comp (ref "R36")
      (value "RES0603")
      (footprint "eagle-import:R0603")
      (libsource (lib "eagle-import") (part "RES0603"))
    )
    (comp (ref "R37")
      (value "RES0603")
      (footprint "eagle-import:R0603")
      (libsource (lib "eagle-import") (part "RES0603"))
    )
    (comp (ref "R38")
      (value "RES0603")
      (footprint "eagle-import:R0603")
      (libsource (lib "eagle-import") (part "RES0603"))
    )
    (comp (ref "R39")
      (value "RES0603")
      (footprint "eagle-import:R0603")
      (libsource (lib "eagle-import") (part "RES0603"))
    )
    (comp (ref "R40")
      (value "RES0603")
      (footprint "eagle-import:R0603")
      (libsource (lib "eagle-import") (part "RES0603"))
    )
    (comp (ref "R42")
      (value "RES0603")
      (footprint "eagle-import:R0603")
      (libsource (lib "eagle-import") (part "RES0603"))
    )
    (comp (ref "R43")
      (value "RES0603")
      (footprint "eagle-import:R0603")
      (libsource (lib "eagle-import") (part "RES0603"))
    )
    (comp (ref "R44")
      (value "RES-ARRAY-1206")
      (footprint "eagle-import:RA1206-8")
      (libsource (lib "eagle-import") (part "RES-ARRAY-1206"))
    )
    (comp (ref "R45")
      (value "RES0603")
      (footprint "eagle-import:R0603")
      (libsource (lib "eagle-import") (part "RES0603"))
    )
    (comp (ref "R46")
      (value "RES0603")
      (footprint "eagle-import:R0603")
      (libsource (lib "eagle-import") (part "RES0603"))
    )
    (comp (ref "U$5")
      (value "PSOT23")
      (footprint "eagle-import:SOT23")
      (libsource (lib "eagle-import") (part "PSOT23"))
    )
    (comp (ref "U$6")
      (value "PSOT23")
      (footprint "eagle-import:SOT23")
      (libsource (lib "eagle-import") (part "PSOT23"))
    )
    (comp (ref "U$8")
      (value "NSOT23")
      (footprint "eagle-import:SOT23W")
      (libsource (lib "eagle-import") (part "NSOT23"))
    )
  )
  (nets
    (net (code "1") (name "+5V") (class "Default")
      (node (ref "C1") (pin "+") (pinfunction "+_+") (pintype "passive"))
      (node (ref "C2") (pin "2") (pinfunction "P$2_2") (pintype "bidirectional"))
      (node (ref "C3") (pin "2") (pinfunction "P$2_2") (pintype "bidirectional"))
      (node (ref "C44") (pin "+") (pinfunction "+_+") (pintype "passive"))
      (node (ref "C45") (pin "+") (pinfunction "+_+") (pintype "passive"))
      (node (ref "C46") (pin "+") (pinfunction "+_+") (pintype "passive"))
      (node (ref "C5") (pin "2") (pinfunction "P$2_2") (pintype "bidirectional"))
      (node (ref "I2C") (pin "1") (pinfunction "1_1") (pintype "passive"))
      (node (ref "JP1") (pin "1") (pinfunction "1_1") (pintype "passive"))
      (node (ref "LCD") (pin "9") (pinfunction "9_9") (pintype "passive"))
      (node (ref "LED_DR1") (pin "8") (pinfunction "OUT_8") (pintype "bidirectional"))
      (node (ref "LED_DR2") (pin "8") (pinfunction "OUT_8") (pintype "bidirectional"))
      (node (ref "MOTOR_CONTROL") (pin "2") (pinfunction "2_2") (pintype "passive"))
      (node (ref "POTENTIOMETR") (pin "6") (pinfunction "6_6") (pintype "passive"))
      (node (ref "POWER") (pin "1") (pinfunction "1_1") (pintype "passive"))
      (node (ref "PSOC_UART") (pin "4") (pinfunction "4_4") (pintype "passive"))
      (node (ref "R1") (pin "2") (pinfunction "P$2_2") (pintype "bidirectional"))
      (node (ref "R2") (pin "2") (pinfunction "P$2_2") (pintype "bidirectional"))
      (node (ref "R3") (pin "2") (pinfunction "P$2_2") (pintype "bidirectional"))
      (node (ref "R4") (pin "2") (pinfunction "P$2_2") (pintype "bidirectional"))
      (node (ref "R7") (pin "2") (pinfunction "P$2_2") (pintype "bidirectional"))
      (node (ref "SPEEDOMETR") (pin "1") (pinfunction "1_1") (pintype "passive"))
      (node (ref "U$1") (pin "19") (pinfunction "19_19") (pintype "bidirectional"))
      (node (ref "U$1") (pin "34") (pinfunction "34_34") (pintype "bidirectional"))
      (node (ref "U$1") (pin "35") (pinfunction "35_35") (pintype "bidirectional"))
      (node (ref "U$2") (pin "4") (pinfunction "+5V_4") (pintype "bidirectional"))
    )
    (net (code "2") (name "+15V") (class "Default")
      (node (ref "C12") (pin "+") (pinfunction "+_+") (pintype "passive"))
      (node (ref "DC/DC1") (pin "1") (pinfunction "1_1") (pintype "bidirectional"))
      (node (ref "JP2") (pin "1") (pinfunction "1_1") (pintype "passive"))
      (node (ref "R25") (pin "2") (pinfunction "P$2_2") (pintype "bidirectional"))
      (node (ref "R28") (pin "3") (pinfunction "1_3") (pintype "passive"))
      (node (ref "R42") (pin "1") (pinfunction "P$1_1") (pintype "bidirectional"))
    )
    (net (code "3") (name "ALARM") (class "Default")
      (node (ref "I2C_MASTER") (pin "4") (pinfunction "4_4") (pintype "passive"))
      (node (ref "I2C_SLAVE_1") (pin "4") (pinfunction "4_4") (pintype "passive"))
      (node (ref "I2C_SLAVE_2") (pin "4") (pinfunction "4_4") (pintype "passive"))
      (node (ref "I2C_SLAVE_3") (pin "4") (pinfunction "4_4") (pintype "passive"))
      (node (ref "I2C_SLAVE_4") (pin "4") (pinfunction "4_4") (pintype "passive"))
    )
    (net (code "4") (name "ATM_GND") (class "Default")
      (node (ref "C34") (pin "-") (pinfunction "-_-") (pintype "passive"))
      (node (ref "C35") (pin "2") (pinfunction "2_2") (pintype "passive"))
      (node (ref "C36") (pin "2") (pinfunction "P$2_2") (pintype "bidirectional"))
      (node (ref "C37") (pin "2") (pinfunction "P$2_2") (pintype "bidirectional"))
      (node (ref "C38") (pin "1") (pinfunction "P$1_1") (pintype "bidirectional"))
      (node (ref "C39") (pin "1") (pinfunction "P$1_1") (pintype "bidirectional"))
      (node (ref "C40") (pin "1") (pinfunction "P$1_1") (pintype "bidirectional"))
      (node (ref "C41") (pin "1") (pinfunction "P$1_1") (pintype "bidirectional"))
      (node (ref "C42") (pin "1") (pinfunction "P$1_1") (pintype "bidirectional"))
      (node (ref "C43") (pin "1") (pinfunction "P$1_1") (pintype "bidirectional"))
      (node (ref "GYRO1") (pin "10") (pinfunction "P$10_10") (pintype "bidirectional"))
      (node (ref "GYRO1") (pin "11") (pinfunction "P$11_11") (pintype "bidirectional"))
      (node (ref "GYRO1") (pin "12") (pinfunction "P$12_12") (pintype "bidirectional"))
      (node (ref "GYRO1") (pin "13") (pinfunction "P$13_13") (pintype "bidirectional"))
      (node (ref "GYRO1") (pin "9") (pinfunction "P$9_9") (pintype "bidirectional"))
      (node (ref "JP10") (pin "5") (pinfunction "5_5") (pintype "passive"))
      (node (ref "JP9") (pin "5") (pinfunction "5_5") (pintype "passive"))
      (node (ref "LED15") (pin "C") (pinfunction "C_C") (pintype "passive"))
      (node (ref "LED16") (pin "C") (pinfunction "C_C") (pintype "passive"))
      (node (ref "LIDAR1") (pin "4") (pinfunction "P$4_4") (pintype "bidirectional"))
      (node (ref "SV2") (pin "1") (pinfunction "1_1") (pintype "passive"))
      (node (ref "U$10") (pin "2") (pinfunction "P$3_2") (pintype "bidirectional"))
      (node (ref "U$10") (pin "4") (pinfunction "P$3_4") (pintype "bidirectional"))
      (node (ref "U$9") (pin "GND") (pinfunction "GND_GND") (pintype "bidirectional"))
      (node (ref "U$9") (pin "GND1") (pinfunction "GND1_GND1") (pintype "bidirectional"))
      (node (ref "U$9") (pin "GND2") (pinfunction "GND2_GND2") (pintype "bidirectional"))
    )
    (net (code "5") (name "ATM_RESET") (class "Default")
      (node (ref "JP9") (pin "4") (pinfunction "4_4") (pintype "passive"))
      (node (ref "SV2") (pin "2") (pinfunction "2_2") (pintype "passive"))
      (node (ref "U$9") (pin "C6") (pinfunction "C6_C6") (pintype "bidirectional"))
    )
    (net (code "6") (name "ATM_VCC") (class "Default")
      (node (ref "C34") (pin "+") (pinfunction "+_+") (pintype "passive"))
      (node (ref "C36") (pin "1") (pinfunction "P$1_1") (pintype "bidirectional"))
      (node (ref "C37") (pin "1") (pinfunction "P$1_1") (pintype "bidirectional"))
      (node (ref "C38") (pin "2") (pinfunction "P$2_2") (pintype "bidirectional"))
      (node (ref "C39") (pin "2") (pinfunction "P$2_2") (pintype "bidirectional"))
      (node (ref "C40") (pin "2") (pinfunction "P$2_2") (pintype "bidirectional"))
      (node (ref "C41") (pin "2") (pinfunction "P$2_2") (pintype "bidirectional"))
      (node (ref "GYRO1") (pin "1") (pinfunction "P$1_1") (pintype "bidirectional"))
      (node (ref "GYRO1") (pin "16") (pinfunction "P$16_16") (pintype "bidirectional"))
      (node (ref "JP10") (pin "1") (pinfunction "1_1") (pintype "passive"))
      (node (ref "JP9") (pin "1") (pinfunction "1_1") (pintype "passive"))
      (node (ref "LIDAR1") (pin "1") (pinfunction "P$1_1") (pintype "bidirectional"))
      (node (ref "R49") (pin "2") (pinfunction "P$2_2") (pintype "bidirectional"))
      (node (ref "R51") (pin "1") (pinfunction "P$1_1") (pintype "bidirectional"))
      (node (ref "SV2") (pin "5") (pinfunction "5_5") (pintype "passive"))
      (node (ref "U$9") (pin "ADC6") (pinfunction "ADC6_ADC6") (pintype "bidirectional"))
      (node (ref "U$9") (pin "AREF") (pinfunction "AREF_AREF") (pintype "bidirectional"))
      (node (ref "U$9") (pin "VCC") (pinfunction "VCC_VCC") (pintype "bidirectional"))
      (node (ref "U$9") (pin "VCC1") (pinfunction "VCC1_VCC1") (pintype "bidirectional"))
    )
    (net (code "7") (name "B1") (class "Default")
      (node (ref "POTENTIOMETR") (pin "3") (pinfunction "3_3") (pintype "passive"))
      (node (ref "U$1") (pin "16") (pinfunction "16_16") (pintype "bidirectional"))
    )
    (net (code "8") (name "B1_CHARGE_EN") (class "Default")
      (node (ref "BAT_CONTROL") (pin "7") (pinfunction "7_7") (pintype "passive"))
      (node (ref "U$1") (pin "12") (pinfunction "12_12") (pintype "bidirectional"))
    )
    (net (code "9") (name "B1_PL") (class "Default")
      (node (ref "BAT_CONTROL") (pin "2") (pinfunction "2_2") (pintype "passive"))
      (node (ref "U$1") (pin "2") (pinfunction "2_2") (pintype "bidirectional"))
    )
    (net (code "10") (name "B1_TEMP") (class "Default")
      (node (ref "BAT_CONTROL") (pin "6") (pinfunction "6_6") (pintype "passive"))
      (node (ref "U$1") (pin "4") (pinfunction "4_4") (pintype "bidirectional"))
    )
    (net (code "11") (name "B2") (class "Default")
      (node (ref "POTENTIOMETR") (pin "1") (pinfunction "1_1") (pintype "passive"))
      (node (ref "U$1") (pin "17") (pinfunction "17_17") (pintype "bidirectional"))
    )
    (net (code "12") (name "B2_CHARGE_EN") (class "Default")
      (node (ref "BAT_CONTROL") (pin "9") (pinfunction "9_9") (pintype "passive"))
      (node (ref "U$1") (pin "15") (pinfunction "15_15") (pintype "bidirectional"))
    )
    (net (code "13") (name "B2_PL") (class "Default")
      (node (ref "BAT_CONTROL") (pin "4") (pinfunction "4_4") (pintype "passive"))
      (node (ref "U$1") (pin "3") (pinfunction "3_3") (pintype "bidirectional"))
    )
    (net (code "14") (name "B2_TEMP") (class "Default")
      (node (ref "BAT_CONTROL") (pin "8") (pinfunction "8_8") (pintype "passive"))
      (node (ref "U$1") (pin "5") (pinfunction "5_5") (pintype "bidirectional"))
    )
    (net (code "15") (name "B3") (class "Default")
      (node (ref "POTENTIOMETR") (pin "2") (pinfunction "2_2") (pintype "passive"))
      (node (ref "U$1") (pin "31") (pinfunction "31_31") (pintype "bidirectional"))
    )
    (net (code "16") (name "BAT1_CHARGE_EN") (class "Default")
      (node (ref "BAT_CTRL") (pin "7") (pinfunction "7_7") (pintype "passive"))
      (node (ref "R24") (pin "1") (pinfunction "P$1_1") (pintype "bidirectional"))
    )
    (net (code "17") (name "BAT1_EN") (class "Default")
      (node (ref "BAT_CONTROL") (pin "10") (pinfunction "10_10") (pintype "passive"))
      (node (ref "U$1") (pin "6") (pinfunction "6_6") (pintype "bidirectional"))
    )
    (net (code "18") (name "BAT1_OUT_EN") (class "Default")
      (node (ref "BAT_CTRL") (pin "10") (pinfunction "10_10") (pintype "passive"))
      (node (ref "R23") (pin "1") (pinfunction "P$1_1") (pintype "bidirectional"))
      (node (ref "R44") (pin "2") (pinfunction "1_2") (pintype "passive"))
    )
    (net (code "19") (name "BAT1_PL") (class "Default")
      (node (ref "BAT_CTRL") (pin "2") (pinfunction "2_2") (pintype "passive"))
      (node (ref "R17") (pin "2") (pinfunction "P$2_2") (pintype "bidirectional"))
      (node (ref "R18") (pin "2") (pinfunction "P$2_2") (pintype "bidirectional"))
    )
    (net (code "20") (name "BAT2_CHARGE_EN") (class "Default")
      (node (ref "BAT_CTRL") (pin "9") (pinfunction "9_9") (pintype "passive"))
      (node (ref "R22") (pin "1") (pinfunction "P$1_1") (pintype "bidirectional"))
    )
    (net (code "21") (name "BAT2_EN") (class "Default")
      (node (ref "BAT_CONTROL") (pin "5") (pinfunction "5_5") (pintype "passive"))
      (node (ref "U$1") (pin "11") (pinfunction "11_11") (pintype "bidirectional"))
    )
    (net (code "22") (name "BAT2_OUT_EN") (class "Default")
      (node (ref "BAT_CTRL") (pin "5") (pinfunction "5_5") (pintype "passive"))
      (node (ref "R21") (pin "1") (pinfunction "P$1_1") (pintype "bidirectional"))
      (node (ref "R28") (pin "1") (pinfunction "1_1") (pintype "passive"))
    )
    (net (code "23") (name "BAT2_PL") (class "Default")
      (node (ref "BAT_CTRL") (pin "4") (pinfunction "4_4") (pintype "passive"))
      (node (ref "R19") (pin "1") (pinfunction "P$1_1") (pintype "bidirectional"))
      (node (ref "R20") (pin "1") (pinfunction "P$1_1") (pintype "bidirectional"))
    )
    (net (code "24") (name "BAT_GND") (class "Default")
      (node (ref "BAT1") (pin "2") (pinfunction "2_2") (pintype "passive"))
      (node (ref "BAT2") (pin "2") (pinfunction "2_2") (pintype "passive"))
      (node (ref "BAT_CTRL") (pin "1") (pinfunction "1_1") (pintype "passive"))
      (node (ref "C12") (pin "-") (pinfunction "-_-") (pintype "passive"))
      (node (ref "C13") (pin "-") (pinfunction "-_-") (pintype "passive"))
      (node (ref "C14") (pin "-") (pinfunction "-_-") (pintype "passive"))
      (node (ref "C15") (pin "1") (pinfunction "P$1_1") (pintype "bidirectional"))
      (node (ref "C17") (pin "-") (pinfunction "-_-") (pintype "passive"))
      (node (ref "C18") (pin "1") (pinfunction "P$1_1") (pintype "bidirectional"))
      (node (ref "C20") (pin "1") (pinfunction "P$1_1") (pintype "bidirectional"))
      (node (ref "C22") (pin "-") (pinfunction "-_-") (pintype "passive"))
      (node (ref "C23") (pin "-") (pinfunction "-_-") (pintype "passive"))
      (node (ref "C24") (pin "1") (pinfunction "P$1_1") (pintype "bidirectional"))
      (node (ref "C25") (pin "1") (pinfunction "P$1_1") (pintype "bidirectional"))
      (node (ref "C28") (pin "1") (pinfunction "P$1_1") (pintype "bidirectional"))
      (node (ref "C29") (pin "-") (pinfunction "-_-") (pintype "passive"))
      (node (ref "C30") (pin "-") (pinfunction "-_-") (pintype "passive"))
      (node (ref "D10") (pin "A") (pinfunction "A_A") (pintype "passive"))
      (node (ref "DC/DC1") (pin "5") (pinfunction "5_5") (pintype "bidirectional"))
      (node (ref "DC/DC1") (pin "7") (pinfunction "7_7") (pintype "bidirectional"))
      (node (ref "DC/DC1") (pin "EPAD") (pinfunction "5_EPAD") (pintype "bidirectional"))
      (node (ref "DC/DC2") (pin "7") (pinfunction "7_7") (pintype "bidirectional"))
      (node (ref "DC/DC3") (pin "2") (pinfunction "7_2") (pintype "bidirectional"))
      (node (ref "DC/DC3") (pin "3") (pinfunction "7_3") (pintype "bidirectional"))
      (node (ref "DC/DC3") (pin "EPAD_BIG") (pinfunction "7_EPAD_BIG") (pintype "bidirectional"))
      (node (ref "DC/DC3") (pin "EPAD_M1") (pinfunction "7_EPAD_M1") (pintype "bidirectional"))
      (node (ref "DC/DC3") (pin "EPAD_M2") (pinfunction "7_EPAD_M2") (pintype "bidirectional"))
      (node (ref "DC/DC3") (pin "EPAD_M3") (pinfunction "7_EPAD_M3") (pintype "bidirectional"))
      (node (ref "DC/DC3") (pin "EPAD_M4") (pinfunction "7_EPAD_M4") (pintype "bidirectional"))
      (node (ref "JP2") (pin "2") (pinfunction "2_2") (pintype "passive"))
      (node (ref "JP4") (pin "2") (pinfunction "2_2") (pintype "passive"))
      (node (ref "JP5") (pin "2") (pinfunction "2_2") (pintype "passive"))
      (node (ref "LED10") (pin "C") (pinfunction "C_C") (pintype "passive"))
      (node (ref "LED11") (pin "C") (pinfunction "C_C") (pintype "passive"))
      (node (ref "LED6") (pin "C") (pinfunction "C_C") (pintype "passive"))
      (node (ref "LED7") (pin "C") (pinfunction "C_C") (pintype "passive"))
      (node (ref "LED8") (pin "C") (pinfunction "C_C") (pintype "passive"))
      (node (ref "LED9") (pin "C") (pinfunction "C_C") (pintype "passive"))
      (node (ref "R17") (pin "1") (pinfunction "P$1_1") (pintype "bidirectional"))
      (node (ref "R19") (pin "2") (pinfunction "P$2_2") (pintype "bidirectional"))
      (node (ref "R26") (pin "2") (pinfunction "P$2_2") (pintype "bidirectional"))
      (node (ref "R29") (pin "1") (pinfunction "P$1_1") (pintype "bidirectional"))
      (node (ref "R30") (pin "1") (pinfunction "P$1_1") (pintype "bidirectional"))
      (node (ref "R32") (pin "1") (pinfunction "P$1_1") (pintype "bidirectional"))
      (node (ref "R33") (pin "1") (pinfunction "P$1_1") (pintype "bidirectional"))
      (node (ref "R35") (pin "1") (pinfunction "P$1_1") (pintype "bidirectional"))
      (node (ref "R36") (pin "1") (pinfunction "P$1_1") (pintype "bidirectional"))
      (node (ref "R38") (pin "1") (pinfunction "P$1_1") (pintype "bidirectional"))
      (node (ref "R40") (pin "1") (pinfunction "P$1_1") (pintype "bidirectional"))
      (node (ref "R43") (pin "1") (pinfunction "P$1_1") (pintype "bidirectional"))
      (node (ref "U$8") (pin "S") (pinfunction "S_S") (pintype "passive"))
    )
    (net (code "25") (name "B_DN") (class "Default")
      (node (ref "B_DN") (pin "4") (pinfunction "A1_4") (pintype "bidirectional"))
      (node (ref "POTENTIOMETR1") (pin "1") (pinfunction "1_1") (pintype "passive"))
    )
    (net (code "26") (name "B_ENT") (class "Default")
      (node (ref "B_EN") (pin "4") (pinfunction "A1_4") (pintype "bidirectional"))
      (node (ref "POTENTIOMETR1") (pin "2") (pinfunction "2_2") (pintype "passive"))
    )
    (net (code "27") (name "B_UP") (class "Default")
      (node (ref "B_UP") (pin "4") (pinfunction "A1_4") (pintype "bidirectional"))
      (node (ref "POTENTIOMETR1") (pin "3") (pinfunction "3_3") (pintype "passive"))
    )
    (net (code "28") (name "CHARGE") (class "Default")
      (node (ref "C17") (pin "+") (pinfunction "+_+") (pintype "passive"))
      (node (ref "D12") (pin "A") (pinfunction "A_A") (pintype "passive"))
      (node (ref "L1") (pin "2") (pinfunction "2_2") (pintype "passive"))
      (node (ref "R27") (pin "1") (pinfunction "P$1_1") (pintype "bidirectional"))
      (node (ref "R28") (pin "2") (pinfunction "1_2") (pintype "passive"))
      (node (ref "U$5") (pin "S") (pinfunction "S_S") (pintype "passive"))
      (node (ref "U$6") (pin "S") (pinfunction "S_S") (pintype "passive"))
    )
    (net (code "29") (name "CHARGE_DETECT") (class "Default")
      (node (ref "BAT_CONTROL") (pin "3") (pinfunction "3_3") (pintype "passive"))
      (node (ref "U$1") (pin "18") (pinfunction "18_18") (pintype "bidirectional"))
    )
    (net (code "30") (name "D4") (class "Default")
      (node (ref "LCD") (pin "7") (pinfunction "7_7") (pintype "passive"))
      (node (ref "U$1") (pin "37") (pinfunction "37_37") (pintype "bidirectional"))
    )
    (net (code "31") (name "D5") (class "Default")
      (node (ref "LCD") (pin "8") (pinfunction "8_8") (pintype "passive"))
      (node (ref "U$1") (pin "38") (pinfunction "38_38") (pintype "bidirectional"))
    )
    (net (code "32") (name "D6") (class "Default")
      (node (ref "LCD") (pin "5") (pinfunction "5_5") (pintype "passive"))
      (node (ref "U$1") (pin "39") (pinfunction "39_39") (pintype "bidirectional"))
    )
    (net (code "33") (name "D7") (class "Default")
      (node (ref "LCD") (pin "6") (pinfunction "6_6") (pintype "passive"))
      (node (ref "U$1") (pin "40") (pinfunction "40_40") (pintype "bidirectional"))
    )
    (net (code "34") (name "DEN") (class "Default")
      (node (ref "GYRO1") (pin "8") (pinfunction "P$8_8") (pintype "bidirectional"))
      (node (ref "U$9") (pin "D7") (pinfunction "D7_D7") (pintype "bidirectional"))
    )
    (net (code "35") (name "E") (class "Default")
      (node (ref "LCD") (pin "3") (pinfunction "3_3") (pintype "passive"))
      (node (ref "U$1") (pin "41") (pinfunction "41_41") (pintype "bidirectional"))
    )
    (net (code "36") (name "EN") (class "Default")
      (node (ref "DC/DC3") (pin "10") (pinfunction "2_10") (pintype "bidirectional"))
      (node (ref "R37") (pin "2") (pinfunction "P$2_2") (pintype "bidirectional"))
      (node (ref "R38") (pin "2") (pinfunction "P$2_2") (pintype "bidirectional"))
    )
    (net (code "37") (name "GND") (class "Default")
      (node (ref "BAT_CONTROL") (pin "1") (pinfunction "1_1") (pintype "passive"))
      (node (ref "C1") (pin "-") (pinfunction "-_-") (pintype "passive"))
      (node (ref "C2") (pin "1") (pinfunction "P$1_1") (pintype "bidirectional"))
      (node (ref "C3") (pin "1") (pinfunction "P$1_1") (pintype "bidirectional"))
      (node (ref "C4") (pin "1") (pinfunction "P$1_1") (pintype "bidirectional"))
      (node (ref "C44") (pin "-") (pinfunction "-_-") (pintype "passive"))
      (node (ref "C45") (pin "-") (pinfunction "-_-") (pintype "passive"))
      (node (ref "C46") (pin "-") (pinfunction "-_-") (pintype "passive"))
      (node (ref "C5") (pin "1") (pinfunction "P$1_1") (pintype "bidirectional"))
      (node (ref "I2C") (pin "5") (pinfunction "5_5") (pintype "passive"))
      (node (ref "JP1") (pin "2") (pinfunction "2_2") (pintype "passive"))
      (node (ref "LCD") (pin "10") (pinfunction "10_10") (pintype "passive"))
      (node (ref "LED1") (pin "C") (pinfunction "C_C") (pintype "passive"))
      (node (ref "LED2") (pin "C") (pinfunction "C_C") (pintype "passive"))
      (node (ref "LED5") (pin "C") (pinfunction "C_C") (pintype "passive"))
      (node (ref "LED_DR1") (pin "4") (pinfunction "OUT_4") (pintype "bidirectional"))
      (node (ref "LED_DR2") (pin "4") (pinfunction "OUT_4") (pintype "bidirectional"))
      (node (ref "MOTOR_CONTROL") (pin "1") (pinfunction "1_1") (pintype "passive"))
      (node (ref "POTENTIOMETR") (pin "5") (pinfunction "5_5") (pintype "passive"))
      (node (ref "POWER") (pin "2") (pinfunction "2_2") (pintype "passive"))
      (node (ref "PSOC_UART") (pin "1") (pinfunction "1_1") (pintype "passive"))
      (node (ref "R10") (pin "1") (pinfunction "P$1_1") (pintype "bidirectional"))
      (node (ref "R11") (pin "1") (pinfunction "P$1_1") (pintype "bidirectional"))
      (node (ref "RGB_1") (pin "4") (pinfunction "4_4") (pintype "passive"))
      (node (ref "RGB_2") (pin "4") (pinfunction "4_4") (pintype "passive"))
      (node (ref "SPEEDOMETR") (pin "3") (pinfunction "3_3") (pintype "passive"))
      (node (ref "U$1") (pin "1") (pinfunction "1_1") (pintype "bidirectional"))
      (node (ref "U$1") (pin "10") (pinfunction "10_10") (pintype "bidirectional"))
      (node (ref "U$1") (pin "36") (pinfunction "36_36") (pintype "bidirectional"))
      (node (ref "U$2") (pin "2") (pinfunction "GND_2") (pintype "bidirectional"))
    )
    (net (code "38") (name "GNDI") (class "Default")
      (node (ref "C10") (pin "1") (pinfunction "P$1_1") (pintype "bidirectional"))
      (node (ref "C11") (pin "2") (pinfunction "P$2_2") (pintype "bidirectional"))
      (node (ref "C6") (pin "1") (pinfunction "P$1_1") (pintype "bidirectional"))
      (node (ref "C7") (pin "1") (pinfunction "P$1_1") (pintype "bidirectional"))
      (node (ref "C8") (pin "1") (pinfunction "P$1_1") (pintype "bidirectional"))
      (node (ref "C9") (pin "2") (pinfunction "P$2_2") (pintype "bidirectional"))
      (node (ref "CP_UART_2") (pin "4") (pinfunction "4_4") (pintype "passive"))
      (node (ref "ESD1") (pin "3") (pinfunction "3_3") (pintype "bidirectional"))
      (node (ref "IC1") (pin "3") (pinfunction "GND_3") (pintype "power_in"))
      (node (ref "IC1") (pin "EXP") (pinfunction "GND_EXP") (pintype "power_in"))
      (node (ref "IC1") (pin "M") (pinfunction "GND_M") (pintype "power_in"))
      (node (ref "IC2") (pin "EPAD") (pinfunction "P$2_EPAD") (pintype "bidirectional"))
      (node (ref "IC2") (pin "P$2") (pinfunction "P$2_P$2") (pintype "bidirectional"))
      (node (ref "IC4") (pin "2") (pinfunction "P$2_2") (pintype "bidirectional"))
      (node (ref "LED3") (pin "C") (pinfunction "C_C") (pintype "passive"))
      (node (ref "LED4") (pin "C") (pinfunction "C_C") (pintype "passive"))
      (node (ref "R12") (pin "1") (pinfunction "P$1_1") (pintype "bidirectional"))
      (node (ref "R15") (pin "1") (pinfunction "P$1_1") (pintype "bidirectional"))
      (node (ref "R9") (pin "1") (pinfunction "P$1_1") (pintype "bidirectional"))
      (node (ref "SW1") (pin "3") (pinfunction "3_3") (pintype "passive"))
      (node (ref "U$3") (pin "GND") (pinfunction "GND_GND") (pintype "bidirectional"))
      (node (ref "U$4") (pin "1") (pinfunction "GND_1") (pintype "power_in"))
      (node (ref "USB1") (pin "10") (pinfunction "P$10_10") (pintype "bidirectional"))
      (node (ref "X1") (pin "4") (pinfunction "4_4") (pintype "passive"))
    )
    (net (code "39") (name "G_MOTOR") (class "Default")
      (node (ref "C31") (pin "-") (pinfunction "-_-") (pintype "passive"))
      (node (ref "C32") (pin "2") (pinfunction "P$2_2") (pintype "bidirectional"))
      (node (ref "C33") (pin "2") (pinfunction "P$2_2") (pintype "bidirectional"))
      (node (ref "DRV1") (pin "1") (pinfunction "1_1") (pintype "bidirectional"))
      (node (ref "DRV1") (pin "7") (pinfunction "1_7") (pintype "bidirectional"))
      (node (ref "DRV1") (pin "EPAD_B") (pinfunction "1_EPAD_B") (pintype "bidirectional"))
      (node (ref "DRV1") (pin "EPAD_T") (pinfunction "1_EPAD_T") (pintype "bidirectional"))
      (node (ref "DRV1") (pin "EPAD_VIA1") (pinfunction "1_EPAD_VIA1") (pintype "bidirectional"))
      (node (ref "DRV1") (pin "EPAD_VIA2") (pinfunction "1_EPAD_VIA2") (pintype "bidirectional"))
      (node (ref "DRV1") (pin "EPAD_VIA3") (pinfunction "1_EPAD_VIA3") (pintype "bidirectional"))
      (node (ref "DRV1") (pin "EPAD_VIA4") (pinfunction "1_EPAD_VIA4") (pintype "bidirectional"))
      (node (ref "DRV1") (pin "EPAD_VIA5") (pinfunction "1_EPAD_VIA5") (pintype "bidirectional"))
      (node (ref "DRV1") (pin "EPAD_VIA6") (pinfunction "1_EPAD_VIA6") (pintype "bidirectional"))
      (node (ref "I_IC1") (pin "P$11") (pinfunction "P$11_P$11") (pintype "bidirectional"))
      (node (ref "I_IC1") (pin "P$6") (pinfunction "P$6_P$6") (pintype "bidirectional"))
      (node (ref "I_IC1") (pin "P$7") (pinfunction "P$7_P$7") (pintype "bidirectional"))
      (node (ref "I_IC1") (pin "P$8") (pinfunction "P$8_P$8") (pintype "bidirectional"))
      (node (ref "JP6") (pin "1") (pinfunction "1_1") (pintype "passive"))
      (node (ref "JP8") (pin "3") (pinfunction "3_3") (pintype "passive"))
      (node (ref "R45") (pin "1") (pinfunction "P$1_1") (pintype "bidirectional"))
      (node (ref "R46") (pin "1") (pinfunction "P$1_1") (pintype "bidirectional"))
    )
    (net (code "40") (name "I2C_GND") (class "Default")
      (node (ref "I2C_MASTER") (pin "5") (pinfunction "5_5") (pintype "passive"))
      (node (ref "I2C_SLAVE_1") (pin "5") (pinfunction "5_5") (pintype "passive"))
      (node (ref "I2C_SLAVE_2") (pin "5") (pinfunction "5_5") (pintype "passive"))
      (node (ref "I2C_SLAVE_3") (pin "5") (pinfunction "5_5") (pintype "passive"))
      (node (ref "I2C_SLAVE_4") (pin "5") (pinfunction "5_5") (pintype "passive"))
    )
    (net (code "41") (name "I2C_SCL") (class "Default")
      (node (ref "I2C_MASTER") (pin "3") (pinfunction "3_3") (pintype "passive"))
      (node (ref "I2C_SLAVE_1") (pin "3") (pinfunction "3_3") (pintype "passive"))
      (node (ref "I2C_SLAVE_2") (pin "3") (pinfunction "3_3") (pintype "passive"))
      (node (ref "I2C_SLAVE_3") (pin "3") (pinfunction "3_3") (pintype "passive"))
      (node (ref "I2C_SLAVE_4") (pin "3") (pinfunction "3_3") (pintype "passive"))
    )
    (net (code "42") (name "I2C_SDA") (class "Default")
      (node (ref "I2C_MASTER") (pin "2") (pinfunction "2_2") (pintype "passive"))
      (node (ref "I2C_SLAVE_1") (pin "2") (pinfunction "2_2") (pintype "passive"))
      (node (ref "I2C_SLAVE_2") (pin "2") (pinfunction "2_2") (pintype "passive"))
      (node (ref "I2C_SLAVE_3") (pin "2") (pinfunction "2_2") (pintype "passive"))
      (node (ref "I2C_SLAVE_4") (pin "2") (pinfunction "2_2") (pintype "passive"))
    )
    (net (code "43") (name "I2C_VCC") (class "Default")
      (node (ref "I2C_MASTER") (pin "1") (pinfunction "1_1") (pintype "passive"))
      (node (ref "I2C_SLAVE_1") (pin "1") (pinfunction "1_1") (pintype "passive"))
      (node (ref "I2C_SLAVE_2") (pin "1") (pinfunction "1_1") (pintype "passive"))
      (node (ref "I2C_SLAVE_3") (pin "1") (pinfunction "1_1") (pintype "passive"))
      (node (ref "I2C_SLAVE_4") (pin "1") (pinfunction "1_1") (pintype "passive"))
    )
    (net (code "44") (name "INT1") (class "Default")
      (node (ref "GYRO1") (pin "7") (pinfunction "P$7_7") (pintype "bidirectional"))
      (node (ref "U$9") (pin "B0") (pinfunction "B0_B0") (pintype "bidirectional"))
    )
    (net (code "45") (name "INT2") (class "Default")
      (node (ref "GYRO1") (pin "6") (pinfunction "P$6_6") (pintype "bidirectional"))
      (node (ref "U$9") (pin "B1") (pinfunction "B1_B1") (pintype "bidirectional"))
    )
    (net (code "46") (name "LCD_PWM") (class "Default")
      (node (ref "LCD") (pin "2") (pinfunction "2_2") (pintype "passive"))
      (node (ref "U$1") (pin "44") (pinfunction "44_44") (pintype "bidirectional"))
    )
    (net (code "47") (name "LED") (class "Default")
      (node (ref "R50") (pin "1") (pinfunction "P$1_1") (pintype "bidirectional"))
      (node (ref "U$9") (pin "C1") (pinfunction "C1_C1") (pintype "bidirectional"))
    )
    (net (code "48") (name "LED_DRIVER") (class "Default")
      (node (ref "LED_DR1") (pin "6") (pinfunction "OUT_6") (pintype "bidirectional"))
      (node (ref "U$1") (pin "22") (pinfunction "22_22") (pintype "bidirectional"))
    )
    (net (code "49") (name "MAIN_VCC") (class "Default")
      (node (ref "C23") (pin "+") (pinfunction "+_+") (pintype "passive"))
      (node (ref "JP4") (pin "1") (pinfunction "1_1") (pintype "passive"))
      (node (ref "L2") (pin "2") (pinfunction "2_2") (pintype "passive"))
      (node (ref "R28") (pin "4") (pinfunction "1_4") (pintype "passive"))
      (node (ref "R34") (pin "2") (pinfunction "P$2_2") (pintype "bidirectional"))
    )
    (net (code "50") (name "MISO") (class "Default")
      (node (ref "GYRO1") (pin "4") (pinfunction "P$4_4") (pintype "bidirectional"))
      (node (ref "SV2") (pin "6") (pinfunction "6_6") (pintype "passive"))
      (node (ref "U$9") (pin "B4") (pinfunction "B4_B4") (pintype "bidirectional"))
    )
    (net (code "51") (name "MOSI") (class "Default")
      (node (ref "GYRO1") (pin "3") (pinfunction "P$3_3") (pintype "bidirectional"))
      (node (ref "SV2") (pin "3") (pinfunction "3_3") (pintype "passive"))
      (node (ref "U$9") (pin "B3") (pinfunction "B3_B3") (pintype "bidirectional"))
    )
    (net (code "52") (name "MOTOR_CURRENT") (class "Default")
      (node (ref "MOTOR_CONTROL") (pin "6") (pinfunction "6_6") (pintype "passive"))
      (node (ref "U$1") (pin "8") (pinfunction "8_8") (pintype "bidirectional"))
    )
    (net (code "53") (name "MOTOR_PWM1") (class "Default")
      (node (ref "MOTOR_CONTROL") (pin "3") (pinfunction "3_3") (pintype "passive"))
      (node (ref "R41") (pin "2") (pinfunction "P$2_2") (pintype "bidirectional"))
      (node (ref "U$1") (pin "23") (pinfunction "23_23") (pintype "bidirectional"))
    )
    (net (code "54") (name "MOTOR_PWM2") (class "Default")
      (node (ref "MOTOR_CONTROL") (pin "5") (pinfunction "5_5") (pintype "passive"))
      (node (ref "R5") (pin "2") (pinfunction "P$2_2") (pintype "bidirectional"))
      (node (ref "U$1") (pin "24") (pinfunction "24_24") (pintype "bidirectional"))
    )
    (net (code "55") (name "MOTOR_TEMP") (class "Default")
      (node (ref "MOTOR_CONTROL") (pin "4") (pinfunction "4_4") (pintype "passive"))
      (node (ref "U$1") (pin "7") (pinfunction "7_7") (pintype "bidirectional"))
    )
    (net (code "56") (name "Net-(BAT_CTRL-Pad3)") (class "Default")
      (node (ref "BAT_CTRL") (pin "3") (pinfunction "3_3") (pintype "passive"))
      (node (ref "U$8") (pin "D") (pinfunction "D_D") (pintype "passive"))
    )
    (net (code "57") (name "Net-(BAT_CTRL-Pad6)") (class "Default")
      (node (ref "BAT_CTRL") (pin "6") (pinfunction "6_6") (pintype "passive"))
      (node (ref "JP3") (pin "1") (pinfunction "1_1") (pintype "passive"))
    )
    (net (code "58") (name "Net-(BAT_CTRL-Pad8)") (class "Default")
      (node (ref "BAT_CTRL") (pin "8") (pinfunction "8_8") (pintype "passive"))
      (node (ref "JP3") (pin "2") (pinfunction "2_2") (pintype "passive"))
    )
    (net (code "59") (name "Net-(C4-P$2)") (class "Default")
      (node (ref "C4") (pin "2") (pinfunction "P$2_2") (pintype "bidirectional"))
      (node (ref "U$1") (pin "33") (pinfunction "33_33") (pintype "bidirectional"))
    )
    (net (code "60") (name "Net-(C7-P$2)") (class "Default")
      (node (ref "C7") (pin "2") (pinfunction "P$2_2") (pintype "bidirectional"))
      (node (ref "IC1") (pin "6") (pinfunction "VDD_6") (pintype "power_in"))
    )
    (net (code "61") (name "Net-(C9-P$1)") (class "Default")
      (node (ref "C9") (pin "1") (pinfunction "P$1_1") (pintype "bidirectional"))
      (node (ref "ESD1") (pin "5") (pinfunction "5_5") (pintype "bidirectional"))
      (node (ref "IC4") (pin "5") (pinfunction "P$5_5") (pintype "bidirectional"))
      (node (ref "R14") (pin "2") (pinfunction "P$2_2") (pintype "bidirectional"))
      (node (ref "R16") (pin "1") (pinfunction "P$1_1") (pintype "bidirectional"))
      (node (ref "R8") (pin "2") (pinfunction "P$2_2") (pintype "bidirectional"))
      (node (ref "U$3") (pin "VCCA") (pinfunction "VCCA_VCCA") (pintype "bidirectional"))
      (node (ref "U$4") (pin "2") (pinfunction "OUT_2") (pintype "power_in"))
      (node (ref "USB1") (pin "12") (pinfunction "P$12_12") (pintype "bidirectional"))
    )
    (net (code "62") (name "Net-(C10-P$2)") (class "Default")
      (node (ref "C10") (pin "2") (pinfunction "P$2_2") (pintype "bidirectional"))
      (node (ref "USB1") (pin "5") (pinfunction "P$5_5") (pintype "bidirectional"))
    )
    (net (code "63") (name "Net-(C11-P$1)") (class "Default")
      (node (ref "C11") (pin "1") (pinfunction "P$1_1") (pintype "bidirectional"))
      (node (ref "USB1") (pin "11") (pinfunction "P$11_11") (pintype "bidirectional"))
    )
    (net (code "64") (name "Net-(C15-P$2)") (class "Default")
      (node (ref "C15") (pin "2") (pinfunction "P$2_2") (pintype "bidirectional"))
      (node (ref "DC/DC1") (pin "4") (pinfunction "4_4") (pintype "bidirectional"))
    )
    (net (code "65") (name "Net-(C16-P$1)") (class "Default")
      (node (ref "C16") (pin "1") (pinfunction "P$1_1") (pintype "bidirectional"))
      (node (ref "D9") (pin "C") (pinfunction "C_C") (pintype "passive"))
      (node (ref "DC/DC1") (pin "9") (pinfunction "9_9") (pintype "bidirectional"))
      (node (ref "L1") (pin "1") (pinfunction "1_1") (pintype "passive"))
    )
    (net (code "66") (name "Net-(C16-P$2)") (class "Default")
      (node (ref "C16") (pin "2") (pinfunction "P$2_2") (pintype "bidirectional"))
      (node (ref "DC/DC1") (pin "10") (pinfunction "10_10") (pintype "bidirectional"))
    )
    (net (code "67") (name "Net-(C18-P$2)") (class "Default")
      (node (ref "C18") (pin "2") (pinfunction "P$2_2") (pintype "bidirectional"))
      (node (ref "C19") (pin "2") (pinfunction "P$2_2") (pintype "bidirectional"))
      (node (ref "DC/DC2") (pin "6") (pinfunction "6_6") (pintype "bidirectional"))
    )
    (net (code "68") (name "Net-(C19-P$1)") (class "Default")
      (node (ref "C19") (pin "1") (pinfunction "P$1_1") (pintype "bidirectional"))
      (node (ref "R32") (pin "2") (pinfunction "P$2_2") (pintype "bidirectional"))
    )
    (net (code "69") (name "Net-(C20-P$2)") (class "Default")
      (node (ref "C20") (pin "2") (pinfunction "P$2_2") (pintype "bidirectional"))
      (node (ref "DC/DC2") (pin "4") (pinfunction "4_4") (pintype "bidirectional"))
    )
    (net (code "70") (name "Net-(C21-P$1)") (class "Default")
      (node (ref "C21") (pin "1") (pinfunction "P$1_1") (pintype "bidirectional"))
      (node (ref "D10") (pin "C") (pinfunction "C_C") (pintype "passive"))
      (node (ref "DC/DC2") (pin "8") (pinfunction "8_8") (pintype "bidirectional"))
      (node (ref "L2") (pin "1") (pinfunction "1_1") (pintype "passive"))
    )
    (net (code "71") (name "Net-(C21-P$2)") (class "Default")
      (node (ref "C21") (pin "2") (pinfunction "P$2_2") (pintype "bidirectional"))
      (node (ref "DC/DC2") (pin "1") (pinfunction "1_1") (pintype "bidirectional"))
    )
    (net (code "72") (name "Net-(C24-P$2)") (class "Default")
      (node (ref "C24") (pin "2") (pinfunction "P$2_2") (pintype "bidirectional"))
      (node (ref "DC/DC3") (pin "9") (pinfunction "5_9") (pintype "bidirectional"))
    )
    (net (code "73") (name "Net-(C25-P$2)") (class "Default")
      (node (ref "C25") (pin "2") (pinfunction "P$2_2") (pintype "bidirectional"))
      (node (ref "C26") (pin "2") (pinfunction "P$2_2") (pintype "bidirectional"))
      (node (ref "DC/DC3") (pin "8") (pinfunction "6_8") (pintype "bidirectional"))
    )
    (net (code "74") (name "Net-(C26-P$1)") (class "Default")
      (node (ref "C26") (pin "1") (pinfunction "P$1_1") (pintype "bidirectional"))
      (node (ref "R36") (pin "2") (pinfunction "P$2_2") (pintype "bidirectional"))
    )
    (net (code "75") (name "Net-(C27-P$1)") (class "Default")
      (node (ref "C27") (pin "1") (pinfunction "P$1_1") (pintype "bidirectional"))
      (node (ref "DC/DC3") (pin "11") (pinfunction "10_11") (pintype "bidirectional"))
      (node (ref "DC/DC3") (pin "12") (pinfunction "10_12") (pintype "bidirectional"))
      (node (ref "L$1") (pin "P$1") (pinfunction "P$1_P$1") (pintype "bidirectional"))
    )
    (net (code "76") (name "Net-(C27-P$2)") (class "Default")
      (node (ref "C27") (pin "2") (pinfunction "P$2_2") (pintype "bidirectional"))
      (node (ref "DC/DC3") (pin "13") (pinfunction "11_13") (pintype "bidirectional"))
    )
    (net (code "77") (name "Net-(C32-P$1)") (class "Default")
      (node (ref "C32") (pin "1") (pinfunction "P$1_1") (pintype "bidirectional"))
      (node (ref "I_IC1") (pin "P$10") (pinfunction "P$10_P$10") (pintype "bidirectional"))
      (node (ref "JP8") (pin "1") (pinfunction "1_1") (pintype "passive"))
      (node (ref "MOTOR_CTRL") (pin "2") (pinfunction "2_2") (pintype "passive"))
    )
    (net (code "78") (name "Net-(C33-P$1)") (class "Default")
      (node (ref "C33") (pin "1") (pinfunction "P$1_1") (pintype "bidirectional"))
      (node (ref "DRV1") (pin "5") (pinfunction "5_5") (pintype "bidirectional"))
      (node (ref "I_IC1") (pin "P$1") (pinfunction "P$1_P$1") (pintype "bidirectional"))
      (node (ref "I_IC1") (pin "P$2") (pinfunction "P$2_P$2") (pintype "bidirectional"))
      (node (ref "I_IC1") (pin "P$3") (pinfunction "P$3_P$3") (pintype "bidirectional"))
    )
    (net (code "79") (name "Net-(C42-P$2)") (class "Default")
      (node (ref "C42") (pin "2") (pinfunction "P$2_2") (pintype "bidirectional"))
      (node (ref "U$10") (pin "3") (pinfunction "P$2_3") (pintype "bidirectional"))
      (node (ref "U$9") (pin "B7") (pinfunction "B7_B7") (pintype "bidirectional"))
    )
    (net (code "80") (name "Net-(C43-P$2)") (class "Default")
      (node (ref "C43") (pin "2") (pinfunction "P$2_2") (pintype "bidirectional"))
      (node (ref "U$10") (pin "1") (pinfunction "P$1_1") (pintype "bidirectional"))
      (node (ref "U$9") (pin "B6") (pinfunction "B6_B6") (pintype "bidirectional"))
    )
    (net (code "81") (name "Net-(CP_UART_2-Pad2)") (class "Default")
      (node (ref "CP_UART_2") (pin "2") (pinfunction "2_2") (pintype "passive"))
      (node (ref "U$3") (pin "B1") (pinfunction "B1_B1") (pintype "bidirectional"))
    )
    (net (code "82") (name "Net-(CP_UART_2-Pad3)") (class "Default")
      (node (ref "CP_UART_2") (pin "3") (pinfunction "3_3") (pintype "passive"))
      (node (ref "U$3") (pin "A1") (pinfunction "A1_A1") (pintype "bidirectional"))
    )
    (net (code "83") (name "Net-(D1-PadA)") (class "Default")
      (node (ref "D1") (pin "A") (pinfunction "A_A") (pintype "passive"))
      (node (ref "U$6") (pin "D") (pinfunction "D_D") (pintype "passive"))
    )
    (net (code "84") (name "Net-(D2-PadA)") (class "Default")
      (node (ref "D2") (pin "A") (pinfunction "A_A") (pintype "passive"))
      (node (ref "D3") (pin "A") (pinfunction "A_A") (pintype "passive"))
      (node (ref "D4") (pin "A") (pinfunction "A_A") (pintype "passive"))
      (node (ref "Q3") (pin "4") (pinfunction "D_4") (pintype "passive"))
      (node (ref "Q3") (pin "D") (pinfunction "D_D") (pintype "passive"))
    )
    (net (code "85") (name "Net-(D5-PadA)") (class "Default")
      (node (ref "D5") (pin "A") (pinfunction "A_A") (pintype "passive"))
      (node (ref "U$5") (pin "D") (pinfunction "D_D") (pintype "passive"))
    )
    (net (code "86") (name "Net-(D6-PadA)") (class "Default")
      (node (ref "D6") (pin "A") (pinfunction "A_A") (pintype "passive"))
      (node (ref "D7") (pin "A") (pinfunction "A_A") (pintype "passive"))
      (node (ref "D8") (pin "A") (pinfunction "A_A") (pintype "passive"))
      (node (ref "Q1") (pin "4") (pinfunction "D_4") (pintype "passive"))
      (node (ref "Q1") (pin "D") (pinfunction "D_D") (pintype "passive"))
    )
    (net (code "87") (name "Net-(DC/DC3-4)") (class "Default")
      (node (ref "DC/DC3") (pin "1") (pinfunction "4_1") (pintype "bidirectional"))
      (node (ref "R35") (pin "2") (pinfunction "P$2_2") (pintype "bidirectional"))
    )
    (net (code "88") (name "Net-(DC/DC3-8)") (class "Default")
      (node (ref "DC/DC3") (pin "6") (pinfunction "8_6") (pintype "bidirectional"))
      (node (ref "R37") (pin "1") (pinfunction "P$1_1") (pintype "bidirectional"))
    )
    (net (code "89") (name "Net-(DC/DC3-9)") (class "Default")
      (node (ref "DC/DC3") (pin "7") (pinfunction "9_7") (pintype "bidirectional"))
      (node (ref "R39") (pin "2") (pinfunction "P$2_2") (pintype "bidirectional"))
      (node (ref "R40") (pin "2") (pinfunction "P$2_2") (pintype "bidirectional"))
    )
    (net (code "90") (name "Net-(DRV1-Pad2)") (class "Default")
      (node (ref "DRV1") (pin "2") (pinfunction "2_2") (pintype "bidirectional"))
      (node (ref "MOTOR_CTRL") (pin "3") (pinfunction "3_3") (pintype "passive"))
    )
    (net (code "91") (name "Net-(DRV1-Pad3)") (class "Default")
      (node (ref "DRV1") (pin "3") (pinfunction "3_3") (pintype "bidirectional"))
      (node (ref "MOTOR_CTRL") (pin "5") (pinfunction "5_5") (pintype "passive"))
    )
    (net (code "92") (name "Net-(DRV1-Pad6)") (class "Default")
      (node (ref "DRV1") (pin "6") (pinfunction "6_6") (pintype "bidirectional"))
      (node (ref "JP7") (pin "1") (pinfunction "1_1") (pintype "passive"))
    )
    (net (code "93") (name "Net-(DRV1-Pad8)") (class "Default")
      (node (ref "DRV1") (pin "8") (pinfunction "8_8") (pintype "bidirectional"))
      (node (ref "JP7") (pin "2") (pinfunction "2_2") (pintype "passive"))
    )
    (net (code "94") (name "Net-(GYRO1-P$14)") (class "Default")
      (node (ref "C35") (pin "1") (pinfunction "1_1") (pintype "passive"))
      (node (ref "GYRO1") (pin "14") (pinfunction "P$14_14") (pintype "bidirectional"))
    )
    (net (code "95") (name "Net-(GYRO1-P$15)") (class "Default")
      (node (ref "GYRO1") (pin "15") (pinfunction "P$15_15") (pintype "bidirectional"))
      (node (ref "R49") (pin "1") (pinfunction "P$1_1") (pintype "bidirectional"))
    )
    (net (code "96") (name "Net-(IC1-D+)") (class "Default")
      (node (ref "ESD1") (pin "1") (pinfunction "1_1") (pintype "bidirectional"))
      (node (ref "IC1") (pin "4") (pinfunction "D+_4") (pintype "bidirectional"))
      (node (ref "USB1") (pin "2") (pinfunction "P$2_2") (pintype "bidirectional"))
    )
    (net (code "97") (name "Net-(IC1-D-)") (class "Default")
      (node (ref "ESD1") (pin "2") (pinfunction "2_2") (pintype "bidirectional"))
      (node (ref "IC1") (pin "5") (pinfunction "D-_5") (pintype "bidirectional"))
      (node (ref "USB1") (pin "1") (pinfunction "P$1_1") (pintype "bidirectional"))
    )
    (net (code "98") (name "Net-(IC1-RXD)") (class "Default")
      (node (ref "IC1") (pin "25") (pinfunction "RXD_25") (pintype "input"))
      (node (ref "U$3") (pin "A2") (pinfunction "A2_A2") (pintype "bidirectional"))
    )
    (net (code "99") (name "Net-(IC1-TXD)") (class "Default")
      (node (ref "IC1") (pin "26") (pinfunction "TXD_26") (pintype "output"))
      (node (ref "U$3") (pin "B2") (pinfunction "B2_B2") (pintype "bidirectional"))
    )
    (net (code "100") (name "Net-(IC1-~{RST})") (class "Default")
      (node (ref "IC1") (pin "9") (pinfunction "~{RST}_9") (pintype "bidirectional"))
      (node (ref "R8") (pin "1") (pinfunction "P$1_1") (pintype "bidirectional"))
    )
    (net (code "101") (name "Net-(IC1-~{SUSPEND})") (class "Default")
      (node (ref "IC1") (pin "11") (pinfunction "~{SUSPEND}_11") (pintype "output"))
      (node (ref "R9") (pin "2") (pinfunction "P$2_2") (pintype "bidirectional"))
    )
    (net (code "102") (name "Net-(IC4-P$1)") (class "Default")
      (node (ref "IC4") (pin "1") (pinfunction "P$1_1") (pintype "bidirectional"))
      (node (ref "SW1") (pin "2") (pinfunction "2_2") (pintype "passive"))
    )
    (net (code "103") (name "Net-(IC4-P$4)") (class "Default")
      (node (ref "CP_UART_2") (pin "1") (pinfunction "1_1") (pintype "passive"))
      (node (ref "IC4") (pin "4") (pinfunction "P$4_4") (pintype "bidirectional"))
      (node (ref "U$3") (pin "OE") (pinfunction "OE_OE") (pintype "bidirectional"))
      (node (ref "U$3") (pin "VCCB") (pinfunction "VCCB_VCCB") (pintype "bidirectional"))
    )
    (net (code "104") (name "Net-(I_IC1-PadP$4)") (class "Default")
      (node (ref "I_IC1") (pin "P$4") (pinfunction "P$4_P$4") (pintype "bidirectional"))
      (node (ref "I_IC1") (pin "P$5") (pinfunction "P$5_P$5") (pintype "bidirectional"))
    )
    (net (code "105") (name "Net-(I_IC1-PadP$9)") (class "Default")
      (node (ref "I_IC1") (pin "P$9") (pinfunction "P$9_P$9") (pintype "bidirectional"))
      (node (ref "MOTOR_CTRL") (pin "6") (pinfunction "6_6") (pintype "passive"))
    )
    (net (code "106") (name "Net-(I_IC1-PadP$12)") (class "Default")
      (node (ref "I_IC1") (pin "P$12") (pinfunction "P$12_P$12") (pintype "bidirectional"))
      (node (ref "I_IC1") (pin "P$13") (pinfunction "P$13_P$13") (pintype "bidirectional"))
    )
    (net (code "107") (name "Net-(JP1-Pad4)") (class "Default")
      (node (ref "JP1") (pin "4") (pinfunction "4_4") (pintype "passive"))
      (node (ref "U$1") (pin "14") (pinfunction "14_14") (pintype "bidirectional"))
    )
    (net (code "108") (name "Net-(JP1-Pad5)") (class "Default")
      (node (ref "JP1") (pin "5") (pinfunction "5_5") (pintype "passive"))
      (node (ref "U$1") (pin "13") (pinfunction "13_13") (pintype "bidirectional"))
    )
    (net (code "109") (name "Net-(JP8-Pad2)") (class "Default")
      (node (ref "JP8") (pin "2") (pinfunction "2_2") (pintype "passive"))
      (node (ref "MOTOR_CTRL") (pin "4") (pinfunction "4_4") (pintype "passive"))
    )
    (net (code "110") (name "Net-(JP9-Pad2)") (class "Default")
      (node (ref "JP9") (pin "2") (pinfunction "2_2") (pintype "passive"))
      (node (ref "U$9") (pin "D1") (pinfunction "D1_D1") (pintype "bidirectional"))
    )
    (net (code "111") (name "Net-(JP9-Pad3)") (class "Default")
      (node (ref "JP9") (pin "3") (pinfunction "3_3") (pintype "passive"))
      (node (ref "U$9") (pin "D0") (pinfunction "D0_D0") (pintype "bidirectional"))
    )
    (net (code "112") (name "Net-(JP10-Pad2)") (class "Default")
      (node (ref "JP10") (pin "2") (pinfunction "2_2") (pintype "passive"))
      (node (ref "U$9") (pin "C4") (pinfunction "C4_C4") (pintype "bidirectional"))
    )
    (net (code "113") (name "Net-(JP10-Pad3)") (class "Default")
      (node (ref "JP10") (pin "3") (pinfunction "3_3") (pintype "passive"))
      (node (ref "U$9") (pin "C5") (pinfunction "C5_C5") (pintype "bidirectional"))
    )
    (net (code "114") (name "Net-(JP10-Pad4)") (class "Default")
      (node (ref "JP10") (pin "4") (pinfunction "4_4") (pintype "passive"))
      (node (ref "U$9") (pin "C3") (pinfunction "C3_C3") (pintype "bidirectional"))
    )
    (net (code "115") (name "Net-(LED_DR1-OUT-Pad1)") (class "Default")
      (node (ref "LED_DR1") (pin "1") (pinfunction "OUT_1") (pintype "bidirectional"))
      (node (ref "RGB_1") (pin "1") (pinfunction "1_1") (pintype "passive"))
    )
    (net (code "116") (name "Net-(LED_DR1-OUT-Pad2)") (class "Default")
      (node (ref "LED_DR1") (pin "2") (pinfunction "OUT_2") (pintype "bidirectional"))
      (node (ref "RGB_1") (pin "2") (pinfunction "2_2") (pintype "passive"))
    )
    (net (code "117") (name "Net-(LED_DR1-OUT-Pad3)") (class "Default")
      (node (ref "LED_DR1") (pin "3") (pinfunction "OUT_3") (pintype "bidirectional"))
      (node (ref "RGB_1") (pin "3") (pinfunction "3_3") (pintype "passive"))
    )
    (net (code "118") (name "Net-(LED_DR1-OUT-Pad5)") (class "Default")
      (node (ref "LED_DR1") (pin "5") (pinfunction "OUT_5") (pintype "bidirectional"))
      (node (ref "LED_DR2") (pin "6") (pinfunction "OUT_6") (pintype "bidirectional"))
    )
    (net (code "119") (name "Net-(LED_DR2-OUT-Pad1)") (class "Default")
      (node (ref "LED_DR2") (pin "1") (pinfunction "OUT_1") (pintype "bidirectional"))
      (node (ref "RGB_2") (pin "1") (pinfunction "1_1") (pintype "passive"))
    )
    (net (code "120") (name "Net-(LED_DR2-OUT-Pad2)") (class "Default")
      (node (ref "LED_DR2") (pin "2") (pinfunction "OUT_2") (pintype "bidirectional"))
      (node (ref "RGB_2") (pin "2") (pinfunction "2_2") (pintype "passive"))
    )
    (net (code "121") (name "Net-(LED_DR2-OUT-Pad3)") (class "Default")
      (node (ref "LED_DR2") (pin "3") (pinfunction "OUT_3") (pintype "bidirectional"))
      (node (ref "RGB_2") (pin "3") (pinfunction "3_3") (pintype "passive"))
    )
    (net (code "122") (name "Net-(LIDAR1-P$2)") (class "Default")
      (node (ref "LIDAR1") (pin "2") (pinfunction "P$2_2") (pintype "bidirectional"))
      (node (ref "U$9") (pin "D2") (pinfunction "D2_D2") (pintype "bidirectional"))
    )
    (net (code "123") (name "Net-(LIDAR1-P$3)") (class "Default")
      (node (ref "LIDAR1") (pin "3") (pinfunction "P$3_3") (pintype "bidirectional"))
      (node (ref "U$9") (pin "D3") (pinfunction "D3_D3") (pintype "bidirectional"))
    )
    (net (code "124") (name "Net-(POTENTIOMETR-Pad4)") (class "Default")
      (node (ref "POTENTIOMETR") (pin "4") (pinfunction "4_4") (pintype "passive"))
      (node (ref "U$1") (pin "9") (pinfunction "9_9") (pintype "bidirectional"))
    )
    (net (code "125") (name "Net-(Q1-G)") (class "Default")
      (node (ref "Q1") (pin "3") (pinfunction "G_3") (pintype "passive"))
      (node (ref "R21") (pin "2") (pinfunction "P$2_2") (pintype "bidirectional"))
    )
    (net (code "126") (name "Net-(Q3-G)") (class "Default")
      (node (ref "Q3") (pin "3") (pinfunction "G_3") (pintype "passive"))
      (node (ref "R23") (pin "2") (pinfunction "P$2_2") (pintype "bidirectional"))
    )
    (net (code "127") (name "Net-(R5-P$1)") (class "Default")
      (node (ref "LED1") (pin "A") (pinfunction "A_A") (pintype "passive"))
      (node (ref "R5") (pin "1") (pinfunction "P$1_1") (pintype "bidirectional"))
    )
    (net (code "128") (name "Net-(R6-P$1)") (class "Default")
      (node (ref "LED2") (pin "A") (pinfunction "A_A") (pintype "passive"))
      (node (ref "R6") (pin "1") (pinfunction "P$1_1") (pintype "bidirectional"))
    )
    (net (code "129") (name "Net-(R6-P$2)") (class "Default")
      (node (ref "R6") (pin "2") (pinfunction "P$2_2") (pintype "bidirectional"))
      (node (ref "U$1") (pin "25") (pinfunction "25_25") (pintype "bidirectional"))
    )
    (net (code "130") (name "Net-(R7-P$1)") (class "Default")
      (node (ref "R7") (pin "1") (pinfunction "P$1_1") (pintype "bidirectional"))
      (node (ref "U$2") (pin "1") (pinfunction "EN_1") (pintype "bidirectional"))
    )
    (net (code "131") (name "Net-(R10-P$2)") (class "Default")
      (node (ref "LED_DR2") (pin "7") (pinfunction "OUT_7") (pintype "bidirectional"))
      (node (ref "R10") (pin "2") (pinfunction "P$2_2") (pintype "bidirectional"))
    )
    (net (code "132") (name "Net-(R11-P$2)") (class "Default")
      (node (ref "LED_DR1") (pin "7") (pinfunction "OUT_7") (pintype "bidirectional"))
      (node (ref "R11") (pin "2") (pinfunction "P$2_2") (pintype "bidirectional"))
    )
    (net (code "133") (name "Net-(R12-P$2)") (class "Default")
      (node (ref "IC2") (pin "P$5") (pinfunction "P$5_P$5") (pintype "bidirectional"))
      (node (ref "R12") (pin "2") (pinfunction "P$2_2") (pintype "bidirectional"))
    )
    (net (code "134") (name "Net-(R13-P$1)") (class "Default")
      (node (ref "LED3") (pin "A") (pinfunction "A_A") (pintype "passive"))
      (node (ref "R13") (pin "1") (pinfunction "P$1_1") (pintype "bidirectional"))
    )
    (net (code "135") (name "Net-(R13-P$2)") (class "Default")
      (node (ref "IC2") (pin "P$1") (pinfunction "P$1_P$1") (pintype "bidirectional"))
      (node (ref "IC2") (pin "P$3") (pinfunction "P$3_P$3") (pintype "bidirectional"))
      (node (ref "R13") (pin "2") (pinfunction "P$2_2") (pintype "bidirectional"))
      (node (ref "X1") (pin "1") (pinfunction "1_1") (pintype "passive"))
    )
    (net (code "136") (name "Net-(R14-P$1)") (class "Default")
      (node (ref "R14") (pin "1") (pinfunction "P$1_1") (pintype "bidirectional"))
      (node (ref "SW1") (pin "1") (pinfunction "1_1") (pintype "passive"))
    )
    (net (code "137") (name "Net-(R15-P$2)") (class "Default")
      (node (ref "R15") (pin "2") (pinfunction "P$2_2") (pintype "bidirectional"))
      (node (ref "USB1") (pin "6") (pinfunction "P$6_6") (pintype "bidirectional"))
    )
    (net (code "138") (name "Net-(R16-P$2)") (class "Default")
      (node (ref "LED4") (pin "A") (pinfunction "A_A") (pintype "passive"))
      (node (ref "R16") (pin "2") (pinfunction "P$2_2") (pintype "bidirectional"))
    )
    (net (code "139") (name "Net-(R18-P$1)") (class "Default")
      (node (ref "BAT1") (pin "1") (pinfunction "1_1") (pintype "passive"))
      (node (ref "C13") (pin "+") (pinfunction "+_+") (pintype "passive"))
      (node (ref "D1") (pin "C") (pinfunction "C_C") (pintype "passive"))
      (node (ref "Q3") (pin "1") (pinfunction "S_1") (pintype "passive"))
      (node (ref "Q3") (pin "2") (pinfunction "S_2") (pintype "passive"))
      (node (ref "Q3") (pin "5") (pinfunction "S_5") (pintype "passive"))
      (node (ref "Q3") (pin "6") (pinfunction "S_6") (pintype "passive"))
      (node (ref "Q3") (pin "S") (pinfunction "S_S") (pintype "passive"))
      (node (ref "R18") (pin "1") (pinfunction "P$1_1") (pintype "bidirectional"))
    )
    (net (code "140") (name "Net-(R20-P$2)") (class "Default")
      (node (ref "BAT2") (pin "1") (pinfunction "1_1") (pintype "passive"))
      (node (ref "C14") (pin "+") (pinfunction "+_+") (pintype "passive"))
      (node (ref "D5") (pin "C") (pinfunction "C_C") (pintype "passive"))
      (node (ref "Q1") (pin "1") (pinfunction "S_1") (pintype "passive"))
      (node (ref "Q1") (pin "2") (pinfunction "S_2") (pintype "passive"))
      (node (ref "Q1") (pin "5") (pinfunction "S_5") (pintype "passive"))
      (node (ref "Q1") (pin "6") (pinfunction "S_6") (pintype "passive"))
      (node (ref "Q1") (pin "S") (pinfunction "S_S") (pintype "passive"))
      (node (ref "R20") (pin "2") (pinfunction "P$2_2") (pintype "bidirectional"))
    )
    (net (code "141") (name "Net-(R22-P$2)") (class "Default")
      (node (ref "R22") (pin "2") (pinfunction "P$2_2") (pintype "bidirectional"))
      (node (ref "U$5") (pin "G") (pinfunction "G_G") (pintype "passive"))
    )
    (net (code "142") (name "Net-(R24-P$2)") (class "Default")
      (node (ref "R24") (pin "2") (pinfunction "P$2_2") (pintype "bidirectional"))
      (node (ref "U$6") (pin "G") (pinfunction "G_G") (pintype "passive"))
    )
    (net (code "143") (name "Net-(R25-P$1)") (class "Default")
      (node (ref "DC/DC1") (pin "2") (pinfunction "2_2") (pintype "bidirectional"))
      (node (ref "R25") (pin "1") (pinfunction "P$1_1") (pintype "bidirectional"))
    )
    (net (code "144") (name "Net-(R26-P$1)") (class "Default")
      (node (ref "DC/DC1") (pin "6") (pinfunction "6_6") (pintype "bidirectional"))
      (node (ref "R26") (pin "1") (pinfunction "P$1_1") (pintype "bidirectional"))
      (node (ref "R27") (pin "2") (pinfunction "P$2_2") (pintype "bidirectional"))
    )
    (net (code "145") (name "Net-(R28A-2)") (class "Default")
      (node (ref "LED9") (pin "A") (pinfunction "A_A") (pintype "passive"))
      (node (ref "R28") (pin "8") (pinfunction "2_8") (pintype "passive"))
    )
    (net (code "146") (name "Net-(R28B-2)") (class "Default")
      (node (ref "LED8") (pin "A") (pinfunction "A_A") (pintype "passive"))
      (node (ref "R28") (pin "7") (pinfunction "2_7") (pintype "passive"))
    )
    (net (code "147") (name "Net-(R28C-2)") (class "Default")
      (node (ref "LED7") (pin "A") (pinfunction "A_A") (pintype "passive"))
      (node (ref "R28") (pin "6") (pinfunction "2_6") (pintype "passive"))
    )
    (net (code "148") (name "Net-(R28D-2)") (class "Default")
      (node (ref "LED6") (pin "A") (pinfunction "A_A") (pintype "passive"))
      (node (ref "R28") (pin "5") (pinfunction "2_5") (pintype "passive"))
    )
    (net (code "149") (name "Net-(R29-P$2)") (class "Default")
      (node (ref "D9") (pin "A") (pinfunction "A_A") (pintype "passive"))
      (node (ref "DC/DC1") (pin "8") (pinfunction "8_8") (pintype "bidirectional"))
      (node (ref "R29") (pin "2") (pinfunction "P$2_2") (pintype "bidirectional"))
    )
    (net (code "150") (name "Net-(R30-P$2)") (class "Default")
      (node (ref "DC/DC2") (pin "3") (pinfunction "3_3") (pintype "bidirectional"))
      (node (ref "R30") (pin "2") (pinfunction "P$2_2") (pintype "bidirectional"))
      (node (ref "R31") (pin "2") (pinfunction "P$2_2") (pintype "bidirectional"))
    )
    (net (code "151") (name "Net-(R31-P$1)") (class "Default")
      (node (ref "C22") (pin "+") (pinfunction "+_+") (pintype "passive"))
      (node (ref "D11") (pin "C") (pinfunction "C_C") (pintype "passive"))
      (node (ref "D12") (pin "C") (pinfunction "C_C") (pintype "passive"))
      (node (ref "DC/DC2") (pin "2") (pinfunction "2_2") (pintype "bidirectional"))
      (node (ref "R31") (pin "1") (pinfunction "P$1_1") (pintype "bidirectional"))
    )
    (net (code "152") (name "Net-(R33-P$2)") (class "Default")
      (node (ref "DC/DC2") (pin "5") (pinfunction "5_5") (pintype "bidirectional"))
      (node (ref "R33") (pin "2") (pinfunction "P$2_2") (pintype "bidirectional"))
      (node (ref "R34") (pin "1") (pinfunction "P$1_1") (pintype "bidirectional"))
    )
    (net (code "153") (name "Net-(R41-P$1)") (class "Default")
      (node (ref "LED5") (pin "A") (pinfunction "A_A") (pintype "passive"))
      (node (ref "R41") (pin "1") (pinfunction "P$1_1") (pintype "bidirectional"))
    )
    (net (code "154") (name "Net-(R42-P$2)") (class "Default")
      (node (ref "R42") (pin "2") (pinfunction "P$2_2") (pintype "bidirectional"))
      (node (ref "R43") (pin "2") (pinfunction "P$2_2") (pintype "bidirectional"))
      (node (ref "U$8") (pin "G") (pinfunction "G_G") (pintype "passive"))
    )
    (net (code "155") (name "Net-(R44A-2)") (class "Default")
      (node (ref "LED11") (pin "A") (pinfunction "A_A") (pintype "passive"))
      (node (ref "R44") (pin "8") (pinfunction "2_8") (pintype "passive"))
    )
    (net (code "156") (name "Net-(R44B-2)") (class "Default")
      (node (ref "LED10") (pin "A") (pinfunction "A_A") (pintype "passive"))
      (node (ref "R44") (pin "7") (pinfunction "2_7") (pintype "passive"))
    )
    (net (code "157") (name "Net-(R45-P$2)") (class "Default")
      (node (ref "DRV1") (pin "4") (pinfunction "4_4") (pintype "bidirectional"))
      (node (ref "R45") (pin "2") (pinfunction "P$2_2") (pintype "bidirectional"))
    )
    (net (code "158") (name "Net-(R46-P$2)") (class "Default")
      (node (ref "MOTOR_CTRL") (pin "1") (pinfunction "1_1") (pintype "passive"))
      (node (ref "R46") (pin "2") (pinfunction "P$2_2") (pintype "bidirectional"))
    )
    (net (code "159") (name "Net-(R47-P$1)") (class "Default")
      (node (ref "LED12") (pin "A") (pinfunction "A_A") (pintype "passive"))
      (node (ref "R47") (pin "1") (pinfunction "P$1_1") (pintype "bidirectional"))
    )
    (net (code "160") (name "Net-(R47-P$2)") (class "Default")
      (node (ref "R47") (pin "2") (pinfunction "P$2_2") (pintype "bidirectional"))
      (node (ref "SV1") (pin "9") (pinfunction "9_9") (pintype "passive"))
      (node (ref "U$7") (pin "2") (pinfunction "P$2_2") (pintype "bidirectional"))
    )
    (net (code "161") (name "Net-(R48-P$1)") (class "Default")
      (node (ref "LED13") (pin "A") (pinfunction "A_A") (pintype "passive"))
      (node (ref "R48") (pin "1") (pinfunction "P$1_1") (pintype "bidirectional"))
    )
    (net (code "162") (name "Net-(R48-P$2)") (class "Default")
      (node (ref "R48") (pin "2") (pinfunction "P$2_2") (pintype "bidirectional"))
      (node (ref "SV1") (pin "2") (pinfunction "2_2") (pintype "passive"))
      (node (ref "U$7") (pin "3") (pinfunction "P$3_3") (pintype "bidirectional"))
    )
    (net (code "163") (name "Net-(R50-P$2)") (class "Default")
      (node (ref "LED15") (pin "A") (pinfunction "A_A") (pintype "passive"))
      (node (ref "R50") (pin "2") (pinfunction "P$2_2") (pintype "bidirectional"))
    )
    (net (code "164") (name "Net-(R51-P$2)") (class "Default")
      (node (ref "LED16") (pin "A") (pinfunction "A_A") (pintype "passive"))
      (node (ref "R51") (pin "2") (pinfunction "P$2_2") (pintype "bidirectional"))
    )
    (net (code "165") (name "Net-(U$2-OUT)") (class "Default")
      (node (ref "U$1") (pin "30") (pinfunction "30_30") (pintype "bidirectional"))
      (node (ref "U$2") (pin "3") (pinfunction "OUT_3") (pintype "bidirectional"))
    )
    (net (code "166") (name "Net-(U$7-P$1)") (class "Default")
      (node (ref "LED12") (pin "C") (pinfunction "C_C") (pintype "passive"))
      (node (ref "LED13") (pin "C") (pinfunction "C_C") (pintype "passive"))
      (node (ref "SV1") (pin "10") (pinfunction "10_10") (pintype "passive"))
      (node (ref "U$7") (pin "1") (pinfunction "P$1_1") (pintype "bidirectional"))
    )
    (net (code "167") (name "Net-(U$7-P$4)") (class "Default")
      (node (ref "SV1") (pin "4") (pinfunction "4_4") (pintype "passive"))
      (node (ref "U$7") (pin "4") (pinfunction "P$4_4") (pintype "bidirectional"))
    )
    (net (code "168") (name "Net-(U$7-P$5)") (class "Default")
      (node (ref "SV1") (pin "1") (pinfunction "1_1") (pintype "passive"))
      (node (ref "U$7") (pin "5") (pinfunction "P$5_5") (pintype "bidirectional"))
    )
    (net (code "169") (name "Net-(U$7-P$6)") (class "Default")
      (node (ref "SV1") (pin "3") (pinfunction "3_3") (pintype "passive"))
      (node (ref "U$7") (pin "6") (pinfunction "P$6_6") (pintype "bidirectional"))
    )
    (net (code "170") (name "Net-(U$7-P$11)") (class "Default")
      (node (ref "SV1") (pin "7") (pinfunction "7_7") (pintype "passive"))
      (node (ref "U$7") (pin "11") (pinfunction "P$11_11") (pintype "bidirectional"))
    )
    (net (code "171") (name "Net-(U$7-P$12)") (class "Default")
      (node (ref "SV1") (pin "8") (pinfunction "8_8") (pintype "passive"))
      (node (ref "U$7") (pin "12") (pinfunction "P$12_12") (pintype "bidirectional"))
    )
    (net (code "172") (name "Net-(U$7-P$13)") (class "Default")
      (node (ref "SV1") (pin "5") (pinfunction "5_5") (pintype "passive"))
      (node (ref "U$7") (pin "13") (pinfunction "P$13_13") (pintype "bidirectional"))
    )
    (net (code "173") (name "Net-(U$7-P$14)") (class "Default")
      (node (ref "SV1") (pin "6") (pinfunction "6_6") (pintype "passive"))
      (node (ref "U$7") (pin "14") (pinfunction "P$14_14") (pintype "bidirectional"))
    )
    (net (code "174") (name "Net-(USB1-P$7)") (class "Default")
      (node (ref "USB1") (pin "7") (pinfunction "P$7_7") (pintype "bidirectional"))
      (node (ref "X1") (pin "3") (pinfunction "3_3") (pintype "passive"))
    )
    (net (code "175") (name "Net-(USB1-P$8)") (class "Default")
      (node (ref "USB1") (pin "8") (pinfunction "P$8_8") (pintype "bidirectional"))
      (node (ref "X1") (pin "2") (pinfunction "2_2") (pintype "passive"))
    )
    (net (code "176") (name "P_GND") (class "Default")
      (node (ref "B_DN") (pin "2") (pinfunction "B0_2") (pintype "bidirectional"))
      (node (ref "B_EN") (pin "2") (pinfunction "B0_2") (pintype "bidirectional"))
      (node (ref "B_UP") (pin "2") (pinfunction "B0_2") (pintype "bidirectional"))
      (node (ref "POTENTIOMETR1") (pin "5") (pinfunction "5_5") (pintype "passive"))
      (node (ref "RV1") (pin "P$3") (pinfunction "A_P$3") (pintype "passive"))
    )
    (net (code "177") (name "P_VCC") (class "Default")
      (node (ref "POTENTIOMETR1") (pin "6") (pinfunction "6_6") (pintype "passive"))
      (node (ref "RV1") (pin "P$1") (pinfunction "E_P$1") (pintype "passive"))
    )
    (net (code "178") (name "RES") (class "Default")
      (node (ref "POTENTIOMETR1") (pin "4") (pinfunction "4_4") (pintype "passive"))
      (node (ref "RV1") (pin "P$2") (pinfunction "S_P$2") (pintype "passive"))
    )
    (net (code "179") (name "RESET") (class "Default")
      (node (ref "JP1") (pin "3") (pinfunction "3_3") (pintype "passive"))
      (node (ref "U$1") (pin "32") (pinfunction "32_32") (pintype "bidirectional"))
    )
    (net (code "180") (name "RS") (class "Default")
      (node (ref "LCD") (pin "4") (pinfunction "4_4") (pintype "passive"))
      (node (ref "U$1") (pin "42") (pinfunction "42_42") (pintype "bidirectional"))
    )
    (net (code "181") (name "RW") (class "Default")
      (node (ref "LCD") (pin "1") (pinfunction "1_1") (pintype "passive"))
      (node (ref "U$1") (pin "43") (pinfunction "43_43") (pintype "bidirectional"))
    )
    (net (code "182") (name "RX") (class "Default")
      (node (ref "PSOC_UART") (pin "3") (pinfunction "3_3") (pintype "passive"))
      (node (ref "R3") (pin "1") (pinfunction "P$1_1") (pintype "bidirectional"))
      (node (ref "U$1") (pin "20") (pinfunction "20_20") (pintype "bidirectional"))
    )
    (net (code "183") (name "SCL") (class "Default")
      (node (ref "I2C") (pin "3") (pinfunction "3_3") (pintype "passive"))
      (node (ref "R2") (pin "1") (pinfunction "P$1_1") (pintype "bidirectional"))
      (node (ref "U$1") (pin "28") (pinfunction "28_28") (pintype "bidirectional"))
    )
    (net (code "184") (name "SCLK") (class "Default")
      (node (ref "GYRO1") (pin "2") (pinfunction "P$2_2") (pintype "bidirectional"))
      (node (ref "SV2") (pin "4") (pinfunction "4_4") (pintype "passive"))
      (node (ref "U$9") (pin "B5") (pinfunction "B5_B5") (pintype "bidirectional"))
    )
    (net (code "185") (name "SDA") (class "Default")
      (node (ref "I2C") (pin "2") (pinfunction "2_2") (pintype "passive"))
      (node (ref "R1") (pin "1") (pinfunction "P$1_1") (pintype "bidirectional"))
      (node (ref "U$1") (pin "29") (pinfunction "29_29") (pintype "bidirectional"))
    )
    (net (code "186") (name "SENSOR_ALARM") (class "Default")
      (node (ref "I2C") (pin "4") (pinfunction "4_4") (pintype "passive"))
      (node (ref "U$1") (pin "27") (pinfunction "27_27") (pintype "bidirectional"))
    )
    (net (code "187") (name "SPEEDOMER") (class "Default")
      (node (ref "SPEEDOMETR") (pin "2") (pinfunction "2_2") (pintype "passive"))
      (node (ref "U$1") (pin "26") (pinfunction "26_26") (pintype "bidirectional"))
    )
    (net (code "188") (name "SS") (class "Default")
      (node (ref "GYRO1") (pin "5") (pinfunction "P$5_5") (pintype "bidirectional"))
      (node (ref "U$9") (pin "B2") (pinfunction "B2_B2") (pintype "bidirectional"))
    )
    (net (code "189") (name "TX") (class "Default")
      (node (ref "PSOC_UART") (pin "2") (pinfunction "2_2") (pintype "passive"))
      (node (ref "R4") (pin "1") (pinfunction "P$1_1") (pintype "bidirectional"))
      (node (ref "U$1") (pin "21") (pinfunction "21_21") (pintype "bidirectional"))
    )
    (net (code "190") (name "VBAT") (class "Default")
      (node (ref "C30") (pin "+") (pinfunction "+_+") (pintype "passive"))
      (node (ref "D11") (pin "A") (pinfunction "A_A") (pintype "passive"))
      (node (ref "D2") (pin "C") (pinfunction "C_C") (pintype "passive"))
      (node (ref "D3") (pin "C") (pinfunction "C_C") (pintype "passive"))
      (node (ref "D4") (pin "C") (pinfunction "C_C") (pintype "passive"))
      (node (ref "D6") (pin "C") (pinfunction "C_C") (pintype "passive"))
      (node (ref "D7") (pin "C") (pinfunction "C_C") (pintype "passive"))
      (node (ref "D8") (pin "C") (pinfunction "C_C") (pintype "passive"))
      (node (ref "DC/DC3") (pin "4") (pinfunction "1_4") (pintype "bidirectional"))
      (node (ref "DC/DC3") (pin "5") (pinfunction "1_5") (pintype "bidirectional"))
    )
    (net (code "191") (name "VBUS") (class "Default")
      (node (ref "C6") (pin "2") (pinfunction "P$2_2") (pintype "bidirectional"))
      (node (ref "C8") (pin "2") (pinfunction "P$2_2") (pintype "bidirectional"))
      (node (ref "IC1") (pin "7") (pinfunction "REGIN_7") (pintype "passive"))
      (node (ref "IC1") (pin "8") (pinfunction "VBUS_8") (pintype "input"))
      (node (ref "IC2") (pin "P$6") (pinfunction "P$6_P$6") (pintype "bidirectional"))
      (node (ref "IC4") (pin "3") (pinfunction "P$3_3") (pintype "bidirectional"))
      (node (ref "U$4") (pin "3") (pinfunction "IN_3") (pintype "power_in"))
    )
    (net (code "192") (name "VMOTOR") (class "Default")
      (node (ref "C28") (pin "2") (pinfunction "P$2_2") (pintype "bidirectional"))
      (node (ref "C29") (pin "+") (pinfunction "+_+") (pintype "passive"))
      (node (ref "JP5") (pin "1") (pinfunction "1_1") (pintype "passive"))
      (node (ref "L$1") (pin "P$2") (pinfunction "P$2_P$2") (pintype "bidirectional"))
      (node (ref "R39") (pin "1") (pinfunction "P$1_1") (pintype "bidirectional"))
      (node (ref "R44") (pin "1") (pinfunction "1_1") (pintype "passive"))
    )
    (net (code "193") (name "V_MOTOR") (class "Default")
      (node (ref "C31") (pin "+") (pinfunction "+_+") (pintype "passive"))
      (node (ref "I_IC1") (pin "P$14") (pinfunction "P$14_P$14") (pintype "bidirectional"))
      (node (ref "I_IC1") (pin "P$15") (pinfunction "P$15_P$15") (pintype "bidirectional"))
      (node (ref "I_IC1") (pin "P$16") (pinfunction "P$16_P$16") (pintype "bidirectional"))
      (node (ref "JP6") (pin "2") (pinfunction "2_2") (pintype "passive"))
    )
    (net (code "194") (name "unconnected-(B_DN-A0-Pad1)") (class "Default")
      (node (ref "B_DN") (pin "1") (pinfunction "A0_1") (pintype "bidirectional"))
    )
    (net (code "195") (name "unconnected-(B_DN-B1-Pad3)") (class "Default")
      (node (ref "B_DN") (pin "3") (pinfunction "B1_3") (pintype "bidirectional"))
    )
    (net (code "196") (name "unconnected-(B_EN-A0-Pad1)") (class "Default")
      (node (ref "B_EN") (pin "1") (pinfunction "A0_1") (pintype "bidirectional"))
    )
    (net (code "197") (name "unconnected-(B_EN-B1-Pad3)") (class "Default")
      (node (ref "B_EN") (pin "3") (pinfunction "B1_3") (pintype "bidirectional"))
    )
    (net (code "198") (name "unconnected-(B_UP-A0-Pad1)") (class "Default")
      (node (ref "B_UP") (pin "1") (pinfunction "A0_1") (pintype "bidirectional"))
    )
    (net (code "199") (name "unconnected-(B_UP-B1-Pad3)") (class "Default")
      (node (ref "B_UP") (pin "3") (pinfunction "B1_3") (pintype "bidirectional"))
    )
    (net (code "200") (name "unconnected-(DC/DC1-Pad3)") (class "Default")
      (node (ref "DC/DC1") (pin "3") (pinfunction "3_3") (pintype "bidirectional"))
    )
    (net (code "201") (name "unconnected-(DC/DC3-3-Pad14)") (class "Default")
      (node (ref "DC/DC3") (pin "14") (pinfunction "3_14") (pintype "bidirectional"))
    )
    (net (code "202") (name "unconnected-(ESD1-Pad4)") (class "Default")
      (node (ref "ESD1") (pin "4") (pinfunction "4_4") (pintype "bidirectional"))
    )
    (net (code "203") (name "unconnected-(IC1-CTS-Pad23)") (class "Default")
      (node (ref "IC1") (pin "23") (pinfunction "CTS_23") (pintype "input"))
    )
    (net (code "204") (name "unconnected-(IC1-DCD-Pad1)") (class "Default")
      (node (ref "IC1") (pin "1") (pinfunction "DCD_1") (pintype "input"))
    )
    (net (code "205") (name "unconnected-(IC1-DSR-Pad27)") (class "Default")
      (node (ref "IC1") (pin "27") (pinfunction "DSR_27") (pintype "input"))
    )
    (net (code "206") (name "unconnected-(IC1-DTR-Pad28)") (class "Default")
      (node (ref "IC1") (pin "28") (pinfunction "DTR_28") (pintype "output"))
    )
    (net (code "207") (name "unconnected-(IC1-RI-Pad2)") (class "Default")
      (node (ref "IC1") (pin "2") (pinfunction "RI_2") (pintype "input"))
    )
    (net (code "208") (name "unconnected-(IC1-RTS-Pad24)") (class "Default")
      (node (ref "IC1") (pin "24") (pinfunction "RTS_24") (pintype "output"))
    )
    (net (code "209") (name "unconnected-(IC1-SUSPEND-Pad12)") (class "Default")
      (node (ref "IC1") (pin "12") (pinfunction "SUSPEND_12") (pintype "output"))
    )
    (net (code "210") (name "unconnected-(IC2-PadP$4)") (class "Default")
      (node (ref "IC2") (pin "P$4") (pinfunction "P$4_P$4") (pintype "bidirectional"))
    )
    (net (code "211") (name "unconnected-(LED_DR2-OUT-Pad5)") (class "Default")
      (node (ref "LED_DR2") (pin "5") (pinfunction "OUT_5") (pintype "bidirectional"))
    )
    (net (code "212") (name "unconnected-(U$7-P$7-Pad7)") (class "Default")
      (node (ref "U$7") (pin "7") (pinfunction "P$7_7") (pintype "bidirectional"))
    )
    (net (code "213") (name "unconnected-(U$7-P$8-Pad8)") (class "Default")
      (node (ref "U$7") (pin "8") (pinfunction "P$8_8") (pintype "bidirectional"))
    )
    (net (code "214") (name "unconnected-(U$7-P$9-Pad9)") (class "Default")
      (node (ref "U$7") (pin "9") (pinfunction "P$9_9") (pintype "bidirectional"))
    )
    (net (code "215") (name "unconnected-(U$7-P$10-Pad10)") (class "Default")
      (node (ref "U$7") (pin "10") (pinfunction "P$10_10") (pintype "bidirectional"))
    )
    (net (code "216") (name "unconnected-(U$9-PadADC7)") (class "Default")
      (node (ref "U$9") (pin "ADC7") (pinfunction "ADC7_ADC7") (pintype "bidirectional"))
    )
    (net (code "217") (name "unconnected-(U$9-PadAVCC)") (class "Default")
      (node (ref "U$9") (pin "AVCC") (pinfunction "AVCC_AVCC") (pintype "bidirectional"))
    )
    (net (code "218") (name "unconnected-(U$9-PadC0)") (class "Default")
      (node (ref "U$9") (pin "C0") (pinfunction "C0_C0") (pintype "bidirectional"))
    )
    (net (code "219") (name "unconnected-(U$9-PadC2)") (class "Default")
      (node (ref "U$9") (pin "C2") (pinfunction "C2_C2") (pintype "bidirectional"))
    )
    (net (code "220") (name "unconnected-(U$9-PadD4)") (class "Default")
      (node (ref "U$9") (pin "D4") (pinfunction "D4_D4") (pintype "bidirectional"))
    )
    (net (code "221") (name "unconnected-(U$9-PadD5)") (class "Default")
      (node (ref "U$9") (pin "D5") (pinfunction "D5_D5") (pintype "bidirectional"))
    )
    (net (code "222") (name "unconnected-(U$9-PadD6)") (class "Default")
      (node (ref "U$9") (pin "D6") (pinfunction "D6_D6") (pintype "bidirectional"))
    )
    (net (code "223") (name "unconnected-(USB1-P$3-Pad3)") (class "Default")
      (node (ref "USB1") (pin "3") (pinfunction "P$3_3") (pintype "bidirectional"))
    )
    (net (code "224") (name "unconnected-(USB1-P$4-Pad4)") (class "Default")
      (node (ref "USB1") (pin "4") (pinfunction "P$4_4") (pintype "bidirectional"))
    )
    (net (code "225") (name "unconnected-(USB1-P$9-Pad9)") (class "Default")
      (node (ref "USB1") (pin "9") (pinfunction "P$9_9") (pintype "bidirectional"))
    )
    (net (code "226") (name "unconnected-(X1-PadS1)") (class "Default")
      (node (ref "X1") (pin "S1") (pinfunction "S1_S1") (pintype "passive"))
    )
    (net (code "227") (name "unconnected-(X1-PadS2)") (class "Default")
      (node (ref "X1") (pin "S2") (pinfunction "S2_S2") (pintype "passive"))
    )
  )
)
